# CHIBI_INPUT_20181126.net
KiCad netlist of a schematic drawn in Altium Designer
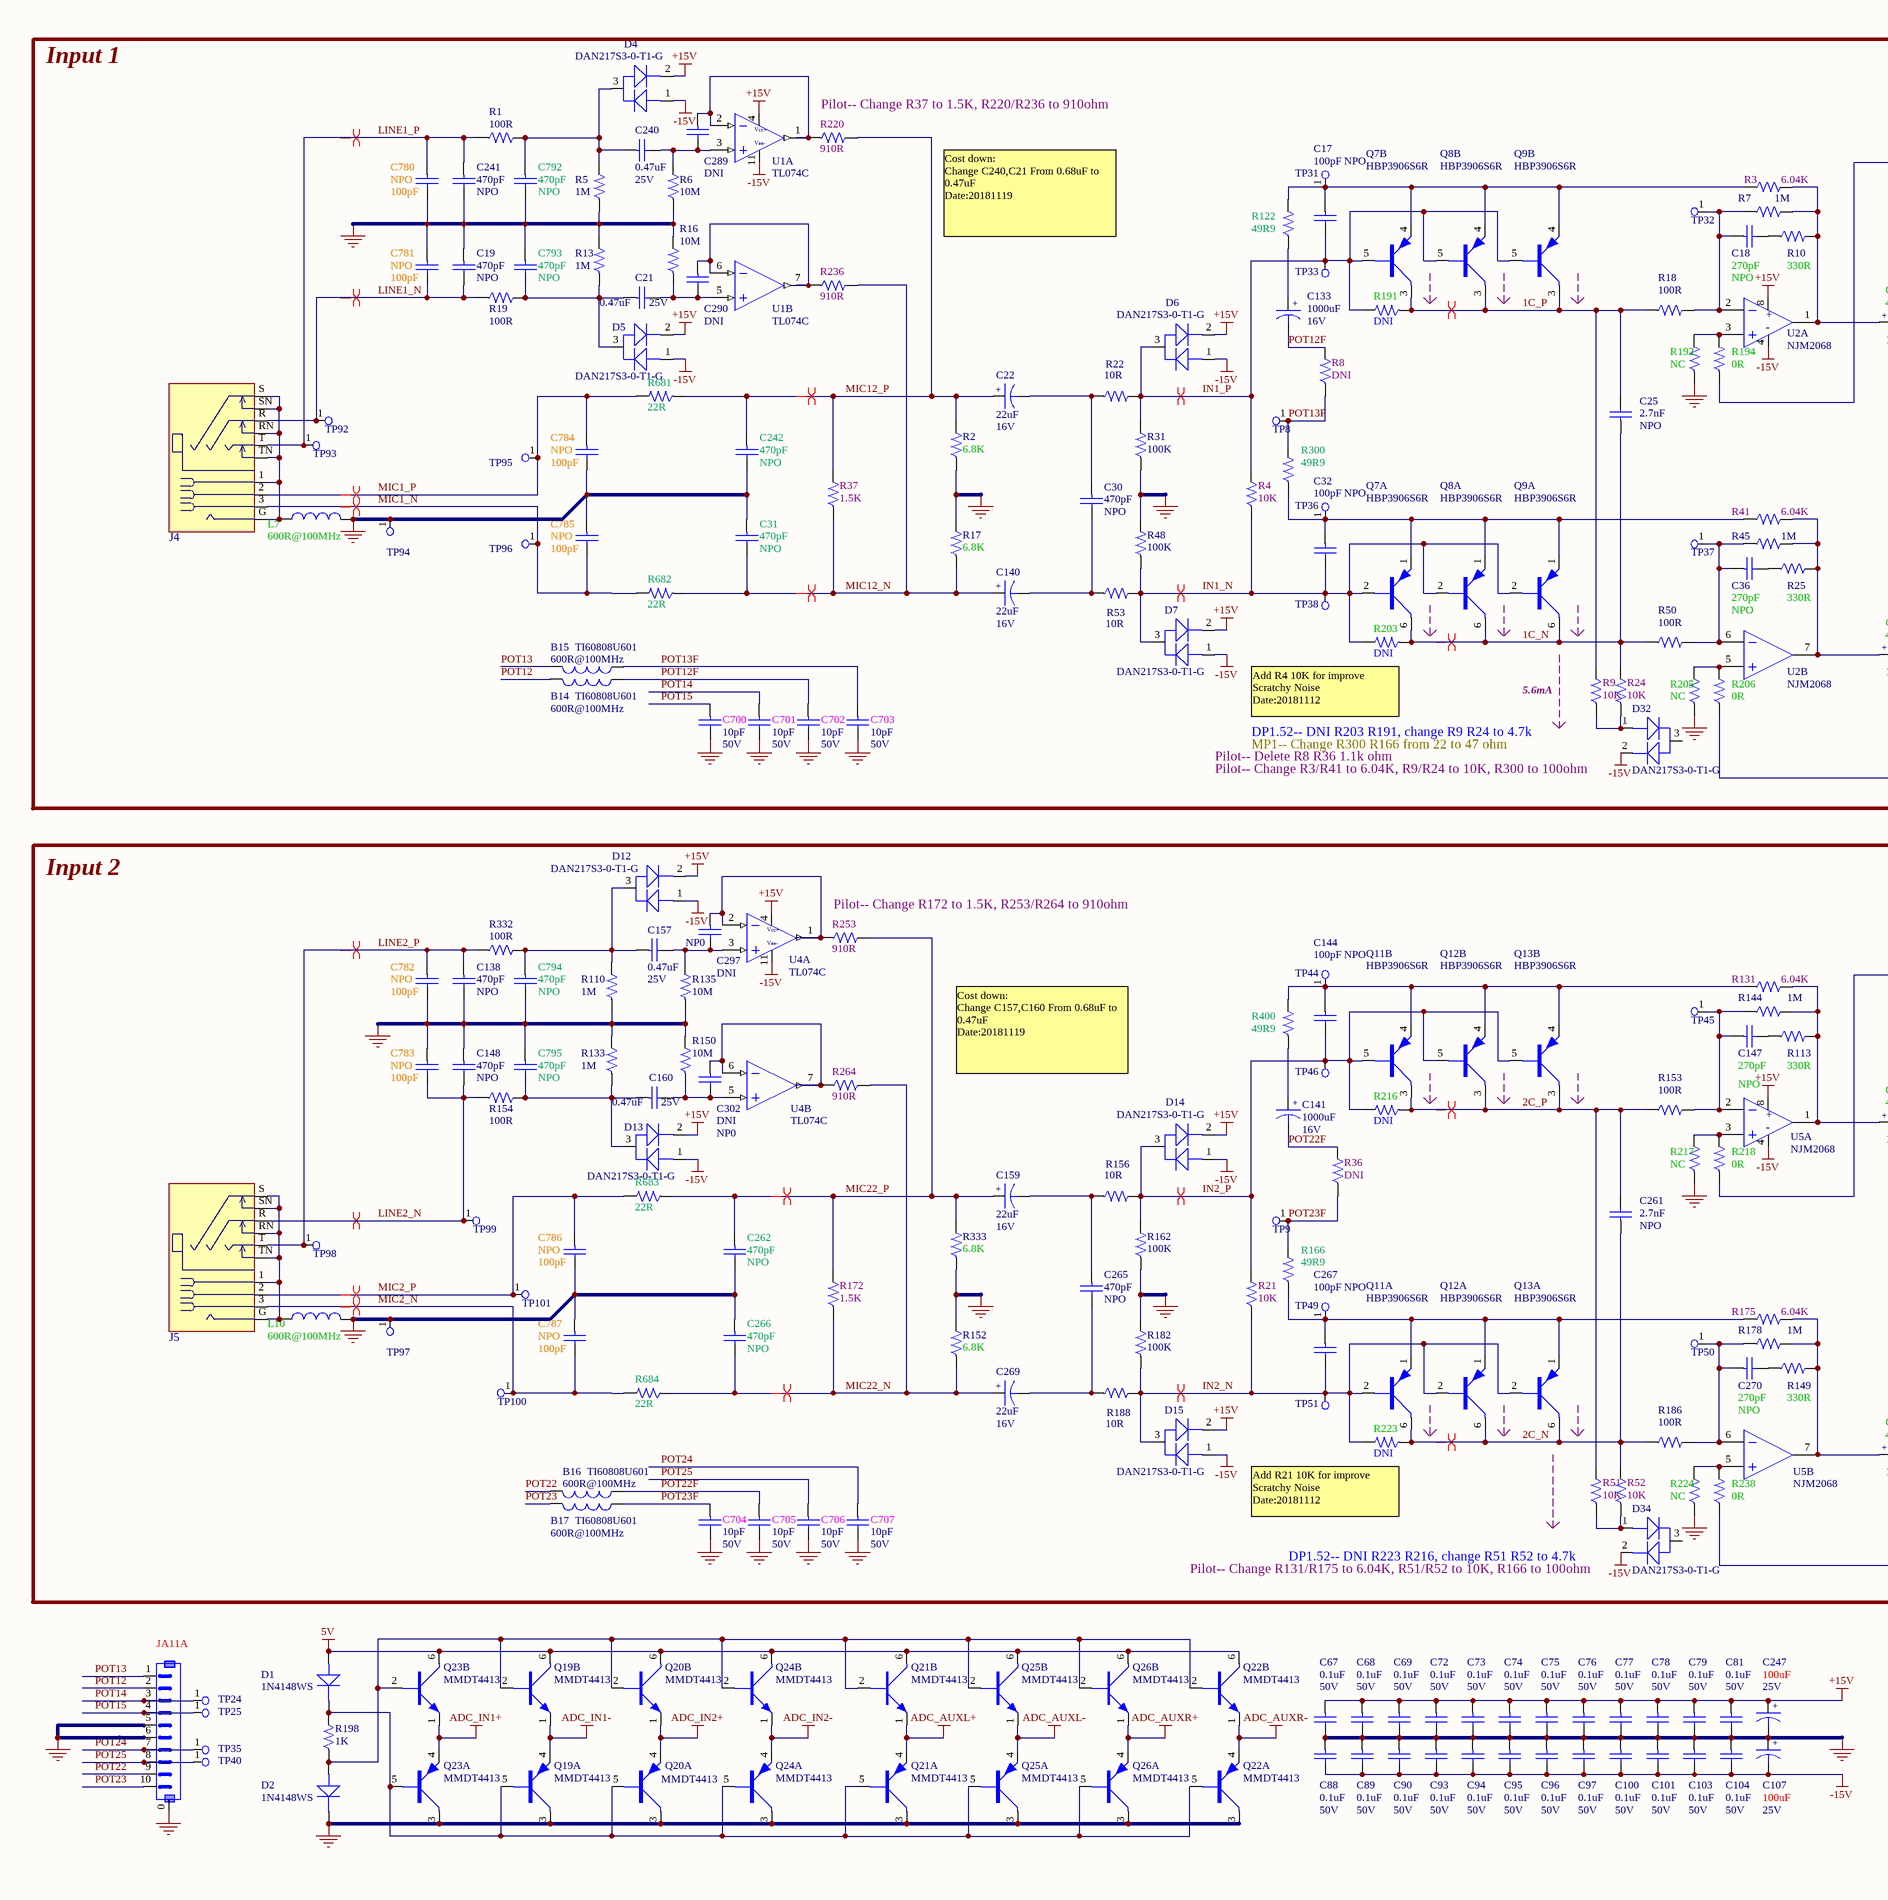
[diagram p0: CHIBI_INPUT_20181126.SchDoc, left]
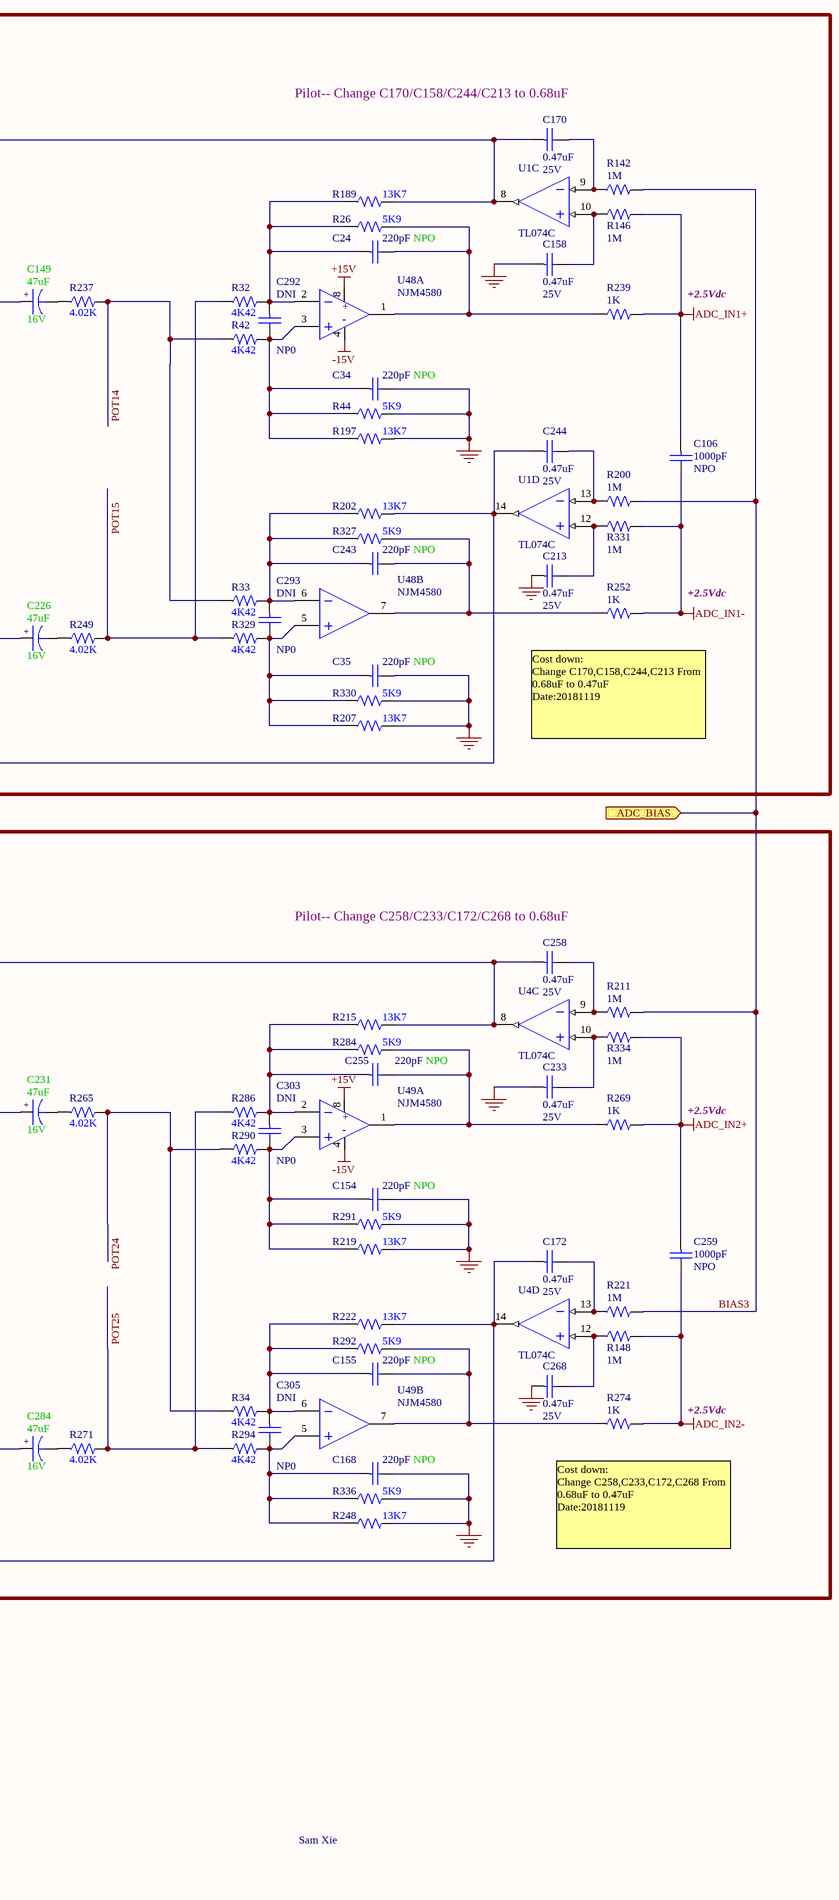
[diagram p1: CHIBI_INPUT_20181126.SchDoc, right]

(export (version "E")
  (design (tool "Eeschema 10.0.6"))
  (components
    (comp (ref "B14")
      (value "600R@100MHz")
      (footprint "L0603-RW")
      (description "CHIP BEAD 600 OHM 25% 100MHZ SMD 0603")
      (fields
        (field (name "MFG") "麦新")
        (field (name "MFG PART") "TI60808U601")
        (field (name "Comment") "SCBA06031-6010")
      )
      (libsource (lib "S-Inductor") (part "BEAD 0603 600R@100MHz TI60808U601"))
    )
    (comp (ref "B15")
      (value "600R@100MHz")
      (footprint "L0603-RW")
      (description "CHIP BEAD 600 OHM 25% 100MHZ SMD 0603")
      (fields
        (field (name "MFG") "麦新")
        (field (name "MFG PART") "TI60808U601")
        (field (name "Comment") "SCBA06031-6010")
      )
      (libsource (lib "S-Inductor") (part "BEAD 0603 600R@100MHz TI60808U601"))
    )
    (comp (ref "B16")
      (value "600R@100MHz")
      (footprint "L0603-RW")
      (description "CHIP BEAD 600 OHM 25% 100MHZ SMD 0603")
      (fields
        (field (name "MFG") "麦新")
        (field (name "MFG PART") "TI60808U601")
        (field (name "Comment") "SCBA06031-6010")
      )
      (libsource (lib "S-Inductor") (part "BEAD 0603 600R@100MHz TI60808U601"))
    )
    (comp (ref "B17")
      (value "600R@100MHz")
      (footprint "L0603-RW")
      (description "CHIP BEAD 600 OHM 25% 100MHZ SMD 0603")
      (fields
        (field (name "MFG") "麦新")
        (field (name "MFG PART") "TI60808U601")
        (field (name "Comment") "SCBA06031-6010")
      )
      (libsource (lib "S-Inductor") (part "BEAD 0603 600R@100MHz TI60808U601"))
    )
    (comp (ref "C17")
      (value "100pF")
      (footprint "CAPC0402-RW")
      (description "CHIP CAP 100pF 50V 5% 0402 TYPE NPO")
      (fields (field (name "MFG") "Walsin") (field (name "OTHER") "NPO") (field (name "TOLERANCE") "5%"))
      (libsource (lib "P-Capacitors") (part "CAP0402 100pF 50V 5%"))
    )
    (comp (ref "C18")
      (value "270pF")
      (footprint "CAPC0603-RW")
      (description "CAP NPO 270PF 50V +-5% 0603 WALSIN L")
      (fields
        (field (name "MFG") "WALSIN")
        (field (name "OTHER") "NPO")
        (field (name "TOLERANCE") "5%")
        (field (name "CREATE_NAME") "Nathan")
      )
      (libsource (lib "P-Capacitors") (part "CAP0603 270pF 50V 5%_NPO_WALSIN"))
    )
    (comp (ref "C19")
      (value "470pF")
      (footprint "CAPC0402-RW")
      (description "CAP CER 470pF 5% 50V NP0/C0G 0402 RoHS")
      (fields
        (field (name "OTHER") "NPO")
        (field (name "TOLERANCE") "5%")
        (field (name "VOLTAGE") "50V")
        (field (name "CREATE_NAME") "TOM@Deftronics")
      )
      (libsource (lib "P-Capacitors") (part "CAP0402 470pF 50V 5% NP0"))
    )
    (comp (ref "C21")
      (value "0.47uF")
      (footprint "CAPC0805X125N-RW")
      (description "CAP X7R .47UF 25V +-10% 0805 WALSIN L")
      (fields
        (field (name "MFG") "WALSIN")
        (field (name "TOLERANCE") "10%")
        (field (name "VOLTAGE") "25V")
        (field (name "CREATE_NAME") "Nathan")
      )
      (libsource (lib "P-Capacitors") (part "CAPC0805 0.47uF 25V 10%_X7R_WALSIN"))
    )
    (comp (ref "C22")
      (value "22uF")
      (footprint "CASE - B")
      (description "E 22UF 16V +-20% 4X5.4M CK1C220M-CRC54 G")
      (fields
        (field (name "MFG") "NORMAL")
        (field (name "MFG PART") "CK1C220M-CRC54")
        (field (name "VOLTAGE") "16V")
      )
      (libsource (lib "P-Capacitors") (part "CAP E 22uF 16V 20% SMD_CASE-B"))
    )
    (comp (ref "C24")
      (value "220pF")
      (footprint "CAPC0603-RW")
      (description "CAP NPO 220PF 50V +-5% 0603 MURATA L")
      (fields
        (field (name "MFG") "MURATA")
        (field (name "OTHER") "NPO")
        (field (name "TOLERANCE") "5%")
        (field (name "CREATE_NAME") "Nathan")
      )
      (libsource (lib "P-Capacitors") (part "CAP0603 220pF 50V 5%_NPO_MURATA"))
    )
    (comp (ref "C25")
      (value "2.7nF")
      (footprint "CAPC0603-RW")
      (description "CHIP CAP 5% 50V 0603 NPO 2.7nF")
      (fields
        (field (name "OTHER") "NPO")
        (field (name "TOLERANCE") "5%")
        (field (name "VOLTAGE") "50V")
        (field (name "CREATE_NAME") "MICHAEL ZHANG")
      )
      (libsource (lib "P-Capacitors") (part "CAP0603 2.7nF 50V 5%"))
    )
    (comp (ref "C30")
      (value "470pF")
      (footprint "CAPC0402-RW")
      (description "CAP CER 470pF 5% 50V NP0/C0G 0402 RoHS")
      (fields
        (field (name "OTHER") "NPO")
        (field (name "TOLERANCE") "5%")
        (field (name "VOLTAGE") "50V")
        (field (name "CREATE_NAME") "TOM@Deftronics")
      )
      (libsource (lib "P-Capacitors") (part "CAP0402 470pF 50V 5% NP0"))
    )
    (comp (ref "C31")
      (value "470pF")
      (footprint "CAPC0402-RW")
      (description "CAP CER 470pF 5% 50V NP0/C0G 0402 RoHS")
      (fields
        (field (name "OTHER") "NPO")
        (field (name "TOLERANCE") "5%")
        (field (name "VOLTAGE") "50V")
        (field (name "CREATE_NAME") "TOM@Deftronics")
      )
      (libsource (lib "P-Capacitors") (part "CAP0402 470pF 50V 5% NP0"))
    )
    (comp (ref "C32")
      (value "100pF")
      (footprint "CAPC0402-RW")
      (description "CHIP CAP 100pF 50V 5% 0402 TYPE NPO")
      (fields (field (name "MFG") "Walsin") (field (name "OTHER") "NPO") (field (name "TOLERANCE") "5%"))
      (libsource (lib "P-Capacitors") (part "CAP0402 100pF 50V 5%"))
    )
    (comp (ref "C34")
      (value "220pF")
      (footprint "CAPC0603-RW")
      (description "CAP NPO 220PF 50V +-5% 0603 MURATA L")
      (fields
        (field (name "MFG") "MURATA")
        (field (name "OTHER") "NPO")
        (field (name "TOLERANCE") "5%")
        (field (name "CREATE_NAME") "Nathan")
      )
      (libsource (lib "P-Capacitors") (part "CAP0603 220pF 50V 5%_NPO_MURATA"))
    )
    (comp (ref "C35")
      (value "220pF")
      (footprint "CAPC0603-RW")
      (description "CAP NPO 220PF 50V +-5% 0603 MURATA L")
      (fields
        (field (name "MFG") "MURATA")
        (field (name "OTHER") "NPO")
        (field (name "TOLERANCE") "5%")
        (field (name "CREATE_NAME") "Nathan")
      )
      (libsource (lib "P-Capacitors") (part "CAP0603 220pF 50V 5%_NPO_MURATA"))
    )
    (comp (ref "C36")
      (value "270pF")
      (footprint "CAPC0603-RW")
      (description "CAP NPO 270PF 50V +-5% 0603 WALSIN L")
      (fields
        (field (name "MFG") "WALSIN")
        (field (name "OTHER") "NPO")
        (field (name "TOLERANCE") "5%")
        (field (name "CREATE_NAME") "Nathan")
      )
      (libsource (lib "P-Capacitors") (part "CAP0603 270pF 50V 5%_NPO_WALSIN"))
    )
    (comp (ref "C67")
      (value "0.1uF")
      (footprint "CAPC0402-RW")
      (description "CAP, CER, 0.1uF, 10%, 50V, X7R, 0402, RoHS")
      (fields
        (field (name "TOLERANCE") "10%")
        (field (name "VOLTAGE") "50V")
        (field (name "Comment") "PWL456470-1040")
        (field (name "CREATE_NAME") "TOM@Deftronics")
      )
      (libsource (lib "P-Capacitors") (part "CAP0402 0.1uF 50V 10%"))
    )
    (comp (ref "C68")
      (value "0.1uF")
      (footprint "CAPC0402-RW")
      (description "CAP, CER, 0.1uF, 10%, 50V, X7R, 0402, RoHS")
      (fields
        (field (name "TOLERANCE") "10%")
        (field (name "VOLTAGE") "50V")
        (field (name "Comment") "PWL456470-1040")
        (field (name "CREATE_NAME") "TOM@Deftronics")
      )
      (libsource (lib "P-Capacitors") (part "CAP0402 0.1uF 50V 10%"))
    )
    (comp (ref "C69")
      (value "0.1uF")
      (footprint "CAPC0402-RW")
      (description "CAP, CER, 0.1uF, 10%, 50V, X7R, 0402, RoHS")
      (fields
        (field (name "TOLERANCE") "10%")
        (field (name "VOLTAGE") "50V")
        (field (name "Comment") "PWL456470-1040")
        (field (name "CREATE_NAME") "TOM@Deftronics")
      )
      (libsource (lib "P-Capacitors") (part "CAP0402 0.1uF 50V 10%"))
    )
    (comp (ref "C72")
      (value "0.1uF")
      (footprint "CAPC0402-RW")
      (description "CAP, CER, 0.1uF, 10%, 50V, X7R, 0402, RoHS")
      (fields
        (field (name "TOLERANCE") "10%")
        (field (name "VOLTAGE") "50V")
        (field (name "Comment") "PWL456470-1040")
        (field (name "CREATE_NAME") "TOM@Deftronics")
      )
      (libsource (lib "P-Capacitors") (part "CAP0402 0.1uF 50V 10%"))
    )
    (comp (ref "C73")
      (value "0.1uF")
      (footprint "CAPC0402-RW")
      (description "CAP, CER, 0.1uF, 10%, 50V, X7R, 0402, RoHS")
      (fields
        (field (name "TOLERANCE") "10%")
        (field (name "VOLTAGE") "50V")
        (field (name "Comment") "PWL456470-1040")
        (field (name "CREATE_NAME") "TOM@Deftronics")
      )
      (libsource (lib "P-Capacitors") (part "CAP0402 0.1uF 50V 10%"))
    )
    (comp (ref "C74")
      (value "0.1uF")
      (footprint "CAPC0402-RW")
      (description "CAP, CER, 0.1uF, 10%, 50V, X7R, 0402, RoHS")
      (fields
        (field (name "TOLERANCE") "10%")
        (field (name "VOLTAGE") "50V")
        (field (name "Comment") "PWL456470-1040")
        (field (name "CREATE_NAME") "TOM@Deftronics")
      )
      (libsource (lib "P-Capacitors") (part "CAP0402 0.1uF 50V 10%"))
    )
    (comp (ref "C75")
      (value "0.1uF")
      (footprint "CAPC0402-RW")
      (description "CAP, CER, 0.1uF, 10%, 50V, X7R, 0402, RoHS")
      (fields
        (field (name "TOLERANCE") "10%")
        (field (name "VOLTAGE") "50V")
        (field (name "Comment") "PWL456470-1040")
        (field (name "CREATE_NAME") "TOM@Deftronics")
      )
      (libsource (lib "P-Capacitors") (part "CAP0402 0.1uF 50V 10%"))
    )
    (comp (ref "C76")
      (value "0.1uF")
      (footprint "CAPC0402-RW")
      (description "CAP, CER, 0.1uF, 10%, 50V, X7R, 0402, RoHS")
      (fields
        (field (name "TOLERANCE") "10%")
        (field (name "VOLTAGE") "50V")
        (field (name "Comment") "PWL456470-1040")
        (field (name "CREATE_NAME") "TOM@Deftronics")
      )
      (libsource (lib "P-Capacitors") (part "CAP0402 0.1uF 50V 10%"))
    )
    (comp (ref "C77")
      (value "0.1uF")
      (footprint "CAPC0402-RW")
      (description "CAP, CER, 0.1uF, 10%, 50V, X7R, 0402, RoHS")
      (fields
        (field (name "TOLERANCE") "10%")
        (field (name "VOLTAGE") "50V")
        (field (name "Comment") "PWL456470-1040")
        (field (name "CREATE_NAME") "TOM@Deftronics")
      )
      (libsource (lib "P-Capacitors") (part "CAP0402 0.1uF 50V 10%"))
    )
    (comp (ref "C78")
      (value "0.1uF")
      (footprint "CAPC0402-RW")
      (description "CAP, CER, 0.1uF, 10%, 50V, X7R, 0402, RoHS")
      (fields
        (field (name "TOLERANCE") "10%")
        (field (name "VOLTAGE") "50V")
        (field (name "Comment") "PWL456470-1040")
        (field (name "CREATE_NAME") "TOM@Deftronics")
      )
      (libsource (lib "P-Capacitors") (part "CAP0402 0.1uF 50V 10%"))
    )
    (comp (ref "C79")
      (value "0.1uF")
      (footprint "CAPC0402-RW")
      (description "CAP, CER, 0.1uF, 10%, 50V, X7R, 0402, RoHS")
      (fields
        (field (name "TOLERANCE") "10%")
        (field (name "VOLTAGE") "50V")
        (field (name "Comment") "PWL456470-1040")
        (field (name "CREATE_NAME") "TOM@Deftronics")
      )
      (libsource (lib "P-Capacitors") (part "CAP0402 0.1uF 50V 10%"))
    )
    (comp (ref "C81")
      (value "0.1uF")
      (footprint "CAPC0402-RW")
      (description "CAP, CER, 0.1uF, 10%, 50V, X7R, 0402, RoHS")
      (fields
        (field (name "TOLERANCE") "10%")
        (field (name "VOLTAGE") "50V")
        (field (name "Comment") "PWL456470-1040")
        (field (name "CREATE_NAME") "TOM@Deftronics")
      )
      (libsource (lib "P-Capacitors") (part "CAP0402 0.1uF 50V 10%"))
    )
    (comp (ref "C88")
      (value "0.1uF")
      (footprint "CAPC0402-RW")
      (description "CAP, CER, 0.1uF, 10%, 50V, X7R, 0402, RoHS")
      (fields
        (field (name "TOLERANCE") "10%")
        (field (name "VOLTAGE") "50V")
        (field (name "Comment") "PWL456470-1040")
        (field (name "CREATE_NAME") "TOM@Deftronics")
      )
      (libsource (lib "P-Capacitors") (part "CAP0402 0.1uF 50V 10%"))
    )
    (comp (ref "C89")
      (value "0.1uF")
      (footprint "CAPC0402-RW")
      (description "CAP, CER, 0.1uF, 10%, 50V, X7R, 0402, RoHS")
      (fields
        (field (name "TOLERANCE") "10%")
        (field (name "VOLTAGE") "50V")
        (field (name "Comment") "PWL456470-1040")
        (field (name "CREATE_NAME") "TOM@Deftronics")
      )
      (libsource (lib "P-Capacitors") (part "CAP0402 0.1uF 50V 10%"))
    )
    (comp (ref "C90")
      (value "0.1uF")
      (footprint "CAPC0402-RW")
      (description "CAP, CER, 0.1uF, 10%, 50V, X7R, 0402, RoHS")
      (fields
        (field (name "TOLERANCE") "10%")
        (field (name "VOLTAGE") "50V")
        (field (name "Comment") "PWL456470-1040")
        (field (name "CREATE_NAME") "TOM@Deftronics")
      )
      (libsource (lib "P-Capacitors") (part "CAP0402 0.1uF 50V 10%"))
    )
    (comp (ref "C93")
      (value "0.1uF")
      (footprint "CAPC0402-RW")
      (description "CAP, CER, 0.1uF, 10%, 50V, X7R, 0402, RoHS")
      (fields
        (field (name "TOLERANCE") "10%")
        (field (name "VOLTAGE") "50V")
        (field (name "Comment") "PWL456470-1040")
        (field (name "CREATE_NAME") "TOM@Deftronics")
      )
      (libsource (lib "P-Capacitors") (part "CAP0402 0.1uF 50V 10%"))
    )
    (comp (ref "C94")
      (value "0.1uF")
      (footprint "CAPC0402-RW")
      (description "CAP, CER, 0.1uF, 10%, 50V, X7R, 0402, RoHS")
      (fields
        (field (name "TOLERANCE") "10%")
        (field (name "VOLTAGE") "50V")
        (field (name "Comment") "PWL456470-1040")
        (field (name "CREATE_NAME") "TOM@Deftronics")
      )
      (libsource (lib "P-Capacitors") (part "CAP0402 0.1uF 50V 10%"))
    )
    (comp (ref "C95")
      (value "0.1uF")
      (footprint "CAPC0402-RW")
      (description "CAP, CER, 0.1uF, 10%, 50V, X7R, 0402, RoHS")
      (fields
        (field (name "TOLERANCE") "10%")
        (field (name "VOLTAGE") "50V")
        (field (name "Comment") "PWL456470-1040")
        (field (name "CREATE_NAME") "TOM@Deftronics")
      )
      (libsource (lib "P-Capacitors") (part "CAP0402 0.1uF 50V 10%"))
    )
    (comp (ref "C96")
      (value "0.1uF")
      (footprint "CAPC0402-RW")
      (description "CAP, CER, 0.1uF, 10%, 50V, X7R, 0402, RoHS")
      (fields
        (field (name "TOLERANCE") "10%")
        (field (name "VOLTAGE") "50V")
        (field (name "Comment") "PWL456470-1040")
        (field (name "CREATE_NAME") "TOM@Deftronics")
      )
      (libsource (lib "P-Capacitors") (part "CAP0402 0.1uF 50V 10%"))
    )
    (comp (ref "C97")
      (value "0.1uF")
      (footprint "CAPC0402-RW")
      (description "CAP, CER, 0.1uF, 10%, 50V, X7R, 0402, RoHS")
      (fields
        (field (name "TOLERANCE") "10%")
        (field (name "VOLTAGE") "50V")
        (field (name "Comment") "PWL456470-1040")
        (field (name "CREATE_NAME") "TOM@Deftronics")
      )
      (libsource (lib "P-Capacitors") (part "CAP0402 0.1uF 50V 10%"))
    )
    (comp (ref "C100")
      (value "0.1uF")
      (footprint "CAPC0402-RW")
      (description "CAP, CER, 0.1uF, 10%, 50V, X7R, 0402, RoHS")
      (fields
        (field (name "TOLERANCE") "10%")
        (field (name "VOLTAGE") "50V")
        (field (name "Comment") "PWL456470-1040")
        (field (name "CREATE_NAME") "TOM@Deftronics")
      )
      (libsource (lib "P-Capacitors") (part "CAP0402 0.1uF 50V 10%"))
    )
    (comp (ref "C101")
      (value "0.1uF")
      (footprint "CAPC0402-RW")
      (description "CAP, CER, 0.1uF, 10%, 50V, X7R, 0402, RoHS")
      (fields
        (field (name "TOLERANCE") "10%")
        (field (name "VOLTAGE") "50V")
        (field (name "Comment") "PWL456470-1040")
        (field (name "CREATE_NAME") "TOM@Deftronics")
      )
      (libsource (lib "P-Capacitors") (part "CAP0402 0.1uF 50V 10%"))
    )
    (comp (ref "C103")
      (value "0.1uF")
      (footprint "CAPC0402-RW")
      (description "CAP, CER, 0.1uF, 10%, 50V, X7R, 0402, RoHS")
      (fields
        (field (name "TOLERANCE") "10%")
        (field (name "VOLTAGE") "50V")
        (field (name "Comment") "PWL456470-1040")
        (field (name "CREATE_NAME") "TOM@Deftronics")
      )
      (libsource (lib "P-Capacitors") (part "CAP0402 0.1uF 50V 10%"))
    )
    (comp (ref "C104")
      (value "0.1uF")
      (footprint "CAPC0402-RW")
      (description "CAP, CER, 0.1uF, 10%, 50V, X7R, 0402, RoHS")
      (fields
        (field (name "TOLERANCE") "10%")
        (field (name "VOLTAGE") "50V")
        (field (name "Comment") "PWL456470-1040")
        (field (name "CREATE_NAME") "TOM@Deftronics")
      )
      (libsource (lib "P-Capacitors") (part "CAP0402 0.1uF 50V 10%"))
    )
    (comp (ref "C106")
      (value "1000pF")
      (footprint "CAPC0603-RW")
      (description "CHIP CAP 1000pF 50V 5% 0603 TYPE NPO")
      (fields (field (name "OTHER") "NPO") (field (name "TOLERANCE") "5%") (field (name "VOLTAGE") "50V"))
      (libsource (lib "P-Capacitors") (part "CAP0603 1000pF 50V 5% - PXL410370-1020"))
    )
    (comp (ref "C107")
      (value "100uF")
      (footprint "CASE - D8")
      (description "E 100UF 25V +-20% 6.3*7. DV101M025 G")
      (fields
        (field (name "MFG") "CAPXON")
        (field (name "MFG PART") "DV101M025E077ETR")
        (field (name "VOLTAGE") "25V")
        (field (name "CREATE_NAME") "Tom")
      )
      (libsource (lib "P-Capacitors") (part "CAP E 100uF 25V 20% SMD"))
    )
    (comp (ref "C133")
      (value "1000uF")
      (footprint "CAP_Radial_D8L16P3.5")
      (description "COND ELECT 1000uF 16V 20% 105C LOW ESR")
      (fields (field (name "MFG") "佳维诚") (field (name "TOLERANCE") "20%") (field (name "VOLTAGE") "16V"))
      (libsource (lib "P-Capacitors") (part "CAP E Aluminum 1000uF 16V 20%"))
    )
    (comp (ref "C138")
      (value "470pF")
      (footprint "CAPC0402-RW")
      (description "CAP CER 470pF 5% 50V NP0/C0G 0402 RoHS")
      (fields
        (field (name "OTHER") "NPO")
        (field (name "TOLERANCE") "5%")
        (field (name "VOLTAGE") "50V")
        (field (name "CREATE_NAME") "TOM@Deftronics")
      )
      (libsource (lib "P-Capacitors") (part "CAP0402 470pF 50V 5% NP0"))
    )
    (comp (ref "C140")
      (value "22uF")
      (footprint "CASE - B")
      (description "E 22UF 16V +-20% 4X5.4M CK1C220M-CRC54 G")
      (fields
        (field (name "MFG") "NORMAL")
        (field (name "MFG PART") "CK1C220M-CRC54")
        (field (name "VOLTAGE") "16V")
      )
      (libsource (lib "P-Capacitors") (part "CAP E 22uF 16V 20% SMD_CASE-B"))
    )
    (comp (ref "C141")
      (value "1000uF")
      (footprint "CAP_Radial_D8L16P3.5")
      (description "COND ELECT 1000uF 16V 20% 105C LOW ESR")
      (fields (field (name "MFG") "佳维诚") (field (name "TOLERANCE") "20%") (field (name "VOLTAGE") "16V"))
      (libsource (lib "P-Capacitors") (part "CAP E Aluminum 1000uF 16V 20%"))
    )
    (comp (ref "C144")
      (value "100pF")
      (footprint "CAPC0402-RW")
      (description "CHIP CAP 100pF 50V 5% 0402 TYPE NPO")
      (fields (field (name "MFG") "Walsin") (field (name "OTHER") "NPO") (field (name "TOLERANCE") "5%"))
      (libsource (lib "P-Capacitors") (part "CAP0402 100pF 50V 5%"))
    )
    (comp (ref "C147")
      (value "270pF")
      (footprint "CAPC0603-RW")
      (description "CAP NPO 270PF 50V +-5% 0603 WALSIN L")
      (fields
        (field (name "MFG") "WALSIN")
        (field (name "OTHER") "NPO")
        (field (name "TOLERANCE") "5%")
        (field (name "CREATE_NAME") "Nathan")
      )
      (libsource (lib "P-Capacitors") (part "CAP0603 270pF 50V 5%_NPO_WALSIN"))
    )
    (comp (ref "C148")
      (value "470pF")
      (footprint "CAPC0402-RW")
      (description "CAP CER 470pF 5% 50V NP0/C0G 0402 RoHS")
      (fields
        (field (name "OTHER") "NPO")
        (field (name "TOLERANCE") "5%")
        (field (name "VOLTAGE") "50V")
        (field (name "CREATE_NAME") "TOM@Deftronics")
      )
      (libsource (lib "P-Capacitors") (part "CAP0402 470pF 50V 5% NP0"))
    )
    (comp (ref "C149")
      (value "47uF")
      (footprint "CASE - C")
      (description "E 47UF 16V +-20% 5X5.4M CK1C470M- G")
      (fields
        (field (name "MFG") "NORMAL")
        (field (name "MFG PART") "CK1C470M-CRD54")
        (field (name "VOLTAGE") "16V")
        (field (name "CREATE_NAME") "Tom")
      )
      (libsource (lib "P-Capacitors") (part "CAP E Aluminum 47uF 16V 20%"))
    )
    (comp (ref "C154")
      (value "220pF")
      (footprint "CAPC0603-RW")
      (description "CAP NPO 220PF 50V +-5% 0603 MURATA L")
      (fields
        (field (name "MFG") "MURATA")
        (field (name "OTHER") "NPO")
        (field (name "TOLERANCE") "5%")
        (field (name "CREATE_NAME") "Nathan")
      )
      (libsource (lib "P-Capacitors") (part "CAP0603 220pF 50V 5%_NPO_MURATA"))
    )
    (comp (ref "C155")
      (value "220pF")
      (footprint "CAPC0603-RW")
      (description "CAP NPO 220PF 50V +-5% 0603 MURATA L")
      (fields
        (field (name "MFG") "MURATA")
        (field (name "OTHER") "NPO")
        (field (name "TOLERANCE") "5%")
        (field (name "CREATE_NAME") "Nathan")
      )
      (libsource (lib "P-Capacitors") (part "CAP0603 220pF 50V 5%_NPO_MURATA"))
    )
    (comp (ref "C157")
      (value "0.47uF")
      (footprint "CAPC0805X125N-RW")
      (description "CAP X7R .47UF 25V +-10% 0805 WALSIN L")
      (fields
        (field (name "MFG") "WALSIN")
        (field (name "TOLERANCE") "10%")
        (field (name "VOLTAGE") "25V")
        (field (name "CREATE_NAME") "Nathan")
      )
      (libsource (lib "P-Capacitors") (part "CAPC0805 0.47uF 25V 10%_X7R_WALSIN"))
    )
    (comp (ref "C158")
      (value "0.47uF")
      (footprint "CAPC0805X125N-RW")
      (description "CAP X7R .47UF 25V +-10% 0805 WALSIN L")
      (fields
        (field (name "MFG") "WALSIN")
        (field (name "TOLERANCE") "10%")
        (field (name "VOLTAGE") "25V")
        (field (name "CREATE_NAME") "Nathan")
      )
      (libsource (lib "P-Capacitors") (part "CAPC0805 0.47uF 25V 10%_X7R_WALSIN"))
    )
    (comp (ref "C159")
      (value "22uF")
      (footprint "CASE - B")
      (description "E 22UF 16V +-20% 4X5.4M CK1C220M-CRC54 G")
      (fields
        (field (name "MFG") "NORMAL")
        (field (name "MFG PART") "CK1C220M-CRC54")
        (field (name "VOLTAGE") "16V")
      )
      (libsource (lib "P-Capacitors") (part "CAP E 22uF 16V 20% SMD_CASE-B"))
    )
    (comp (ref "C160")
      (value "0.47uF")
      (footprint "CAPC0805X125N-RW")
      (description "CAP X7R .47UF 25V +-10% 0805 WALSIN L")
      (fields
        (field (name "MFG") "WALSIN")
        (field (name "TOLERANCE") "10%")
        (field (name "VOLTAGE") "25V")
        (field (name "CREATE_NAME") "Nathan")
      )
      (libsource (lib "P-Capacitors") (part "CAPC0805 0.47uF 25V 10%_X7R_WALSIN"))
    )
    (comp (ref "C168")
      (value "220pF")
      (footprint "CAPC0603-RW")
      (description "CAP NPO 220PF 50V +-5% 0603 MURATA L")
      (fields
        (field (name "MFG") "MURATA")
        (field (name "OTHER") "NPO")
        (field (name "TOLERANCE") "5%")
        (field (name "CREATE_NAME") "Nathan")
      )
      (libsource (lib "P-Capacitors") (part "CAP0603 220pF 50V 5%_NPO_MURATA"))
    )
    (comp (ref "C170")
      (value "0.47uF")
      (footprint "CAPC0805X125N-RW")
      (description "CAP X7R .47UF 25V +-10% 0805 WALSIN L")
      (fields
        (field (name "MFG") "WALSIN")
        (field (name "TOLERANCE") "10%")
        (field (name "VOLTAGE") "25V")
        (field (name "CREATE_NAME") "Nathan")
      )
      (libsource (lib "P-Capacitors") (part "CAPC0805 0.47uF 25V 10%_X7R_WALSIN"))
    )
    (comp (ref "C172")
      (value "0.47uF")
      (footprint "CAPC0805X125N-RW")
      (description "CAP X7R .47UF 25V +-10% 0805 WALSIN L")
      (fields
        (field (name "MFG") "WALSIN")
        (field (name "TOLERANCE") "10%")
        (field (name "VOLTAGE") "25V")
        (field (name "CREATE_NAME") "Nathan")
      )
      (libsource (lib "P-Capacitors") (part "CAPC0805 0.47uF 25V 10%_X7R_WALSIN"))
    )
    (comp (ref "C213")
      (value "0.47uF")
      (footprint "CAPC0805X125N-RW")
      (description "CAP X7R .47UF 25V +-10% 0805 WALSIN L")
      (fields
        (field (name "MFG") "WALSIN")
        (field (name "TOLERANCE") "10%")
        (field (name "VOLTAGE") "25V")
        (field (name "CREATE_NAME") "Nathan")
      )
      (libsource (lib "P-Capacitors") (part "CAPC0805 0.47uF 25V 10%_X7R_WALSIN"))
    )
    (comp (ref "C226")
      (value "47uF")
      (footprint "CASE - C")
      (description "E 47UF 16V +-20% 5X5.4M CK1C470M- G")
      (fields
        (field (name "MFG") "NORMAL")
        (field (name "MFG PART") "CK1C470M-CRD54")
        (field (name "VOLTAGE") "16V")
        (field (name "CREATE_NAME") "Tom")
      )
      (libsource (lib "P-Capacitors") (part "CAP E Aluminum 47uF 16V 20%"))
    )
    (comp (ref "C231")
      (value "47uF")
      (footprint "CASE - C")
      (description "E 47UF 16V +-20% 5X5.4M CK1C470M- G")
      (fields
        (field (name "MFG") "NORMAL")
        (field (name "MFG PART") "CK1C470M-CRD54")
        (field (name "VOLTAGE") "16V")
        (field (name "CREATE_NAME") "Tom")
      )
      (libsource (lib "P-Capacitors") (part "CAP E Aluminum 47uF 16V 20%"))
    )
    (comp (ref "C233")
      (value "0.47uF")
      (footprint "CAPC0805X125N-RW")
      (description "CAP X7R .47UF 25V +-10% 0805 WALSIN L")
      (fields
        (field (name "MFG") "WALSIN")
        (field (name "TOLERANCE") "10%")
        (field (name "VOLTAGE") "25V")
        (field (name "CREATE_NAME") "Nathan")
      )
      (libsource (lib "P-Capacitors") (part "CAPC0805 0.47uF 25V 10%_X7R_WALSIN"))
    )
    (comp (ref "C240")
      (value "0.47uF")
      (footprint "CAPC0805X125N-RW")
      (description "CAP X7R .47UF 25V +-10% 0805 WALSIN L")
      (fields
        (field (name "MFG") "WALSIN")
        (field (name "TOLERANCE") "10%")
        (field (name "VOLTAGE") "25V")
        (field (name "CREATE_NAME") "Nathan")
      )
      (libsource (lib "P-Capacitors") (part "CAPC0805 0.47uF 25V 10%_X7R_WALSIN"))
    )
    (comp (ref "C241")
      (value "470pF")
      (footprint "CAPC0402-RW")
      (description "CAP CER 470pF 5% 50V NP0/C0G 0402 RoHS")
      (fields
        (field (name "OTHER") "NPO")
        (field (name "TOLERANCE") "5%")
        (field (name "VOLTAGE") "50V")
        (field (name "CREATE_NAME") "TOM@Deftronics")
      )
      (libsource (lib "P-Capacitors") (part "CAP0402 470pF 50V 5% NP0"))
    )
    (comp (ref "C242")
      (value "470pF")
      (footprint "CAPC0402-RW")
      (description "CAP CER 470pF 5% 50V NP0/C0G 0402 RoHS")
      (fields
        (field (name "OTHER") "NPO")
        (field (name "TOLERANCE") "5%")
        (field (name "VOLTAGE") "50V")
        (field (name "CREATE_NAME") "TOM@Deftronics")
      )
      (libsource (lib "P-Capacitors") (part "CAP0402 470pF 50V 5% NP0"))
    )
    (comp (ref "C243")
      (value "220pF")
      (footprint "CAPC0603-RW")
      (description "CAP NPO 220PF 50V +-5% 0603 MURATA L")
      (fields
        (field (name "MFG") "MURATA")
        (field (name "OTHER") "NPO")
        (field (name "TOLERANCE") "5%")
        (field (name "CREATE_NAME") "Nathan")
      )
      (libsource (lib "P-Capacitors") (part "CAP0603 220pF 50V 5%_NPO_MURATA"))
    )
    (comp (ref "C244")
      (value "0.47uF")
      (footprint "CAPC0805X125N-RW")
      (description "CAP X7R .47UF 25V +-10% 0805 WALSIN L")
      (fields
        (field (name "MFG") "WALSIN")
        (field (name "TOLERANCE") "10%")
        (field (name "VOLTAGE") "25V")
        (field (name "CREATE_NAME") "Nathan")
      )
      (libsource (lib "P-Capacitors") (part "CAPC0805 0.47uF 25V 10%_X7R_WALSIN"))
    )
    (comp (ref "C247")
      (value "100uF")
      (footprint "CASE - D8")
      (description "E 100UF 25V +-20% 6.3*7. DV101M025 G")
      (fields
        (field (name "MFG") "CAPXON")
        (field (name "MFG PART") "DV101M025E077ETR")
        (field (name "VOLTAGE") "25V")
        (field (name "CREATE_NAME") "Tom")
      )
      (libsource (lib "P-Capacitors") (part "CAP E 100uF 25V 20% SMD"))
    )
    (comp (ref "C255")
      (value "220pF")
      (footprint "CAPC0603-RW")
      (description "CAP NPO 220PF 50V +-5% 0603 MURATA L")
      (fields
        (field (name "MFG") "MURATA")
        (field (name "OTHER") "NPO")
        (field (name "TOLERANCE") "5%")
        (field (name "CREATE_NAME") "Nathan")
      )
      (libsource (lib "P-Capacitors") (part "CAP0603 220pF 50V 5%_NPO_MURATA"))
    )
    (comp (ref "C258")
      (value "0.47uF")
      (footprint "CAPC0805X125N-RW")
      (description "CAP X7R .47UF 25V +-10% 0805 WALSIN L")
      (fields
        (field (name "MFG") "WALSIN")
        (field (name "TOLERANCE") "10%")
        (field (name "VOLTAGE") "25V")
        (field (name "CREATE_NAME") "Nathan")
      )
      (libsource (lib "P-Capacitors") (part "CAPC0805 0.47uF 25V 10%_X7R_WALSIN"))
    )
    (comp (ref "C259")
      (value "1000pF")
      (footprint "CAPC0603-RW")
      (description "CHIP CAP 1000pF 50V 5% 0603 TYPE NPO")
      (fields (field (name "OTHER") "NPO") (field (name "TOLERANCE") "5%") (field (name "VOLTAGE") "50V"))
      (libsource (lib "P-Capacitors") (part "CAP0603 1000pF 50V 5% - PXL410370-1020"))
    )
    (comp (ref "C261")
      (value "2.7nF")
      (footprint "CAPC0603-RW")
      (description "CHIP CAP 5% 50V 0603 NPO 2.7nF")
      (fields
        (field (name "OTHER") "NPO")
        (field (name "TOLERANCE") "5%")
        (field (name "VOLTAGE") "50V")
        (field (name "CREATE_NAME") "MICHAEL ZHANG")
      )
      (libsource (lib "P-Capacitors") (part "CAP0603 2.7nF 50V 5%"))
    )
    (comp (ref "C262")
      (value "470pF")
      (footprint "CAPC0402-RW")
      (description "CAP CER 470pF 5% 50V NP0/C0G 0402 RoHS")
      (fields
        (field (name "OTHER") "NPO")
        (field (name "TOLERANCE") "5%")
        (field (name "VOLTAGE") "50V")
        (field (name "CREATE_NAME") "TOM@Deftronics")
      )
      (libsource (lib "P-Capacitors") (part "CAP0402 470pF 50V 5% NP0"))
    )
    (comp (ref "C265")
      (value "470pF")
      (footprint "CAPC0402-RW")
      (description "CAP CER 470pF 5% 50V NP0/C0G 0402 RoHS")
      (fields
        (field (name "OTHER") "NPO")
        (field (name "TOLERANCE") "5%")
        (field (name "VOLTAGE") "50V")
        (field (name "CREATE_NAME") "TOM@Deftronics")
      )
      (libsource (lib "P-Capacitors") (part "CAP0402 470pF 50V 5% NP0"))
    )
    (comp (ref "C266")
      (value "470pF")
      (footprint "CAPC0402-RW")
      (description "CAP CER 470pF 5% 50V NP0/C0G 0402 RoHS")
      (fields
        (field (name "OTHER") "NPO")
        (field (name "TOLERANCE") "5%")
        (field (name "VOLTAGE") "50V")
        (field (name "CREATE_NAME") "TOM@Deftronics")
      )
      (libsource (lib "P-Capacitors") (part "CAP0402 470pF 50V 5% NP0"))
    )
    (comp (ref "C267")
      (value "100pF")
      (footprint "CAPC0402-RW")
      (description "CHIP CAP 100pF 50V 5% 0402 TYPE NPO")
      (fields (field (name "MFG") "Walsin") (field (name "OTHER") "NPO") (field (name "TOLERANCE") "5%"))
      (libsource (lib "P-Capacitors") (part "CAP0402 100pF 50V 5%"))
    )
    (comp (ref "C268")
      (value "0.47uF")
      (footprint "CAPC0805X125N-RW")
      (description "CAP X7R .47UF 25V +-10% 0805 WALSIN L")
      (fields
        (field (name "MFG") "WALSIN")
        (field (name "TOLERANCE") "10%")
        (field (name "VOLTAGE") "25V")
        (field (name "CREATE_NAME") "Nathan")
      )
      (libsource (lib "P-Capacitors") (part "CAPC0805 0.47uF 25V 10%_X7R_WALSIN"))
    )
    (comp (ref "C269")
      (value "22uF")
      (footprint "CASE - B")
      (description "E 22UF 16V +-20% 4X5.4M CK1C220M-CRC54 G")
      (fields
        (field (name "MFG") "NORMAL")
        (field (name "MFG PART") "CK1C220M-CRC54")
        (field (name "VOLTAGE") "16V")
      )
      (libsource (lib "P-Capacitors") (part "CAP E 22uF 16V 20% SMD_CASE-B"))
    )
    (comp (ref "C270")
      (value "270pF")
      (footprint "CAPC0603-RW")
      (description "CAP NPO 270PF 50V +-5% 0603 WALSIN L")
      (fields
        (field (name "MFG") "WALSIN")
        (field (name "OTHER") "NPO")
        (field (name "TOLERANCE") "5%")
        (field (name "CREATE_NAME") "Nathan")
      )
      (libsource (lib "P-Capacitors") (part "CAP0603 270pF 50V 5%_NPO_WALSIN"))
    )
    (comp (ref "C284")
      (value "47uF")
      (footprint "CASE - C")
      (description "E 47UF 16V +-20% 5X5.4M CK1C470M- G")
      (fields
        (field (name "MFG") "NORMAL")
        (field (name "MFG PART") "CK1C470M-CRD54")
        (field (name "VOLTAGE") "16V")
        (field (name "CREATE_NAME") "Tom")
      )
      (libsource (lib "P-Capacitors") (part "CAP E Aluminum 47uF 16V 20%"))
    )
    (comp (ref "C289")
      (value "DNI")
      (footprint "CAPC0402-RW")
      (fields
        (field (name "TOLERANCE") "10%")
        (field (name "VOLTAGE") "50V")
        (field (name "CREATE_NAME") "Nathan")
      )
      (libsource (lib "P-Capacitors") (part "CAP0402 0.1uF 50V_10%_X7R_TDK"))
    )
    (comp (ref "C290")
      (value "DNI")
      (footprint "CAPC0402-RW")
      (fields
        (field (name "TOLERANCE") "10%")
        (field (name "VOLTAGE") "50V")
        (field (name "CREATE_NAME") "Nathan")
      )
      (libsource (lib "P-Capacitors") (part "CAP0402 0.1uF 50V_10%_X7R_TDK"))
    )
    (comp (ref "C292")
      (value "DNI")
      (footprint "CAPC0402-RW")
      (fields
        (field (name "OTHER") "NP0")
        (field (name "TOLERANCE") "10%")
        (field (name "VOLTAGE") "50V")
        (field (name "CREATE_NAME") "Nathan")
      )
      (libsource (lib "P-Capacitors") (part "CAP0402 0.1uF 50V_10%_X7R_TDK"))
    )
    (comp (ref "C293")
      (value "DNI")
      (footprint "CAPC0402-RW")
      (fields
        (field (name "OTHER") "NP0")
        (field (name "TOLERANCE") "10%")
        (field (name "VOLTAGE") "50V")
        (field (name "CREATE_NAME") "Nathan")
      )
      (libsource (lib "P-Capacitors") (part "CAP0402 0.1uF 50V_10%_X7R_TDK"))
    )
    (comp (ref "C297")
      (value "DNI")
      (footprint "CAPC0402-RW")
      (fields
        (field (name "OTHER") "NP0")
        (field (name "TOLERANCE") "10%")
        (field (name "VOLTAGE") "50V")
        (field (name "CREATE_NAME") "Nathan")
      )
      (libsource (lib "P-Capacitors") (part "CAP0402 0.1uF 50V_10%_X7R_TDK"))
    )
    (comp (ref "C302")
      (value "DNI")
      (footprint "CAPC0402-RW")
      (fields
        (field (name "OTHER") "NP0")
        (field (name "TOLERANCE") "10%")
        (field (name "VOLTAGE") "50V")
        (field (name "CREATE_NAME") "Nathan")
      )
      (libsource (lib "P-Capacitors") (part "CAP0402 0.1uF 50V_10%_X7R_TDK"))
    )
    (comp (ref "C303")
      (value "DNI")
      (footprint "CAPC0402-RW")
      (fields
        (field (name "OTHER") "NP0")
        (field (name "TOLERANCE") "10%")
        (field (name "VOLTAGE") "50V")
        (field (name "CREATE_NAME") "Nathan")
      )
      (libsource (lib "P-Capacitors") (part "CAP0402 0.1uF 50V_10%_X7R_TDK"))
    )
    (comp (ref "C305")
      (value "DNI")
      (footprint "CAPC0402-RW")
      (fields
        (field (name "OTHER") "NP0")
        (field (name "TOLERANCE") "10%")
        (field (name "VOLTAGE") "50V")
        (field (name "CREATE_NAME") "Nathan")
      )
      (libsource (lib "P-Capacitors") (part "CAP0402 0.1uF 50V_10%_X7R_TDK"))
    )
    (comp (ref "C700")
      (value "10pF")
      (footprint "CAPC0402-RW")
      (description "CHIP CAP 5% 50V 0402 NPO 10pF")
      (fields
        (field (name "TOLERANCE") "5%")
        (field (name "VOLTAGE") "50V")
        (field (name "Comment") "PWL410371-1000")
        (field (name "CREATE_NAME") "TOM@Deftronics")
      )
      (libsource (lib "P-Capacitors") (part "CAP0402 10pF 50V 5%"))
    )
    (comp (ref "C701")
      (value "10pF")
      (footprint "CAPC0402-RW")
      (description "CHIP CAP 5% 50V 0402 NPO 10pF")
      (fields
        (field (name "TOLERANCE") "5%")
        (field (name "VOLTAGE") "50V")
        (field (name "Comment") "PWL410371-1000")
        (field (name "CREATE_NAME") "TOM@Deftronics")
      )
      (libsource (lib "P-Capacitors") (part "CAP0402 10pF 50V 5%"))
    )
    (comp (ref "C702")
      (value "10pF")
      (footprint "CAPC0402-RW")
      (description "CHIP CAP 5% 50V 0402 NPO 10pF")
      (fields
        (field (name "TOLERANCE") "5%")
        (field (name "VOLTAGE") "50V")
        (field (name "Comment") "PWL410371-1000")
        (field (name "CREATE_NAME") "TOM@Deftronics")
      )
      (libsource (lib "P-Capacitors") (part "CAP0402 10pF 50V 5%"))
    )
    (comp (ref "C703")
      (value "10pF")
      (footprint "CAPC0402-RW")
      (description "CHIP CAP 5% 50V 0402 NPO 10pF")
      (fields
        (field (name "TOLERANCE") "5%")
        (field (name "VOLTAGE") "50V")
        (field (name "Comment") "PWL410371-1000")
        (field (name "CREATE_NAME") "TOM@Deftronics")
      )
      (libsource (lib "P-Capacitors") (part "CAP0402 10pF 50V 5%"))
    )
    (comp (ref "C704")
      (value "10pF")
      (footprint "CAPC0402-RW")
      (description "CHIP CAP 5% 50V 0402 NPO 10pF")
      (fields
        (field (name "TOLERANCE") "5%")
        (field (name "VOLTAGE") "50V")
        (field (name "Comment") "PWL410371-1000")
        (field (name "CREATE_NAME") "TOM@Deftronics")
      )
      (libsource (lib "P-Capacitors") (part "CAP0402 10pF 50V 5%"))
    )
    (comp (ref "C705")
      (value "10pF")
      (footprint "CAPC0402-RW")
      (description "CHIP CAP 5% 50V 0402 NPO 10pF")
      (fields
        (field (name "TOLERANCE") "5%")
        (field (name "VOLTAGE") "50V")
        (field (name "Comment") "PWL410371-1000")
        (field (name "CREATE_NAME") "TOM@Deftronics")
      )
      (libsource (lib "P-Capacitors") (part "CAP0402 10pF 50V 5%"))
    )
    (comp (ref "C706")
      (value "10pF")
      (footprint "CAPC0402-RW")
      (description "CHIP CAP 5% 50V 0402 NPO 10pF")
      (fields
        (field (name "TOLERANCE") "5%")
        (field (name "VOLTAGE") "50V")
        (field (name "Comment") "PWL410371-1000")
        (field (name "CREATE_NAME") "TOM@Deftronics")
      )
      (libsource (lib "P-Capacitors") (part "CAP0402 10pF 50V 5%"))
    )
    (comp (ref "C707")
      (value "10pF")
      (footprint "CAPC0402-RW")
      (description "CHIP CAP 5% 50V 0402 NPO 10pF")
      (fields
        (field (name "TOLERANCE") "5%")
        (field (name "VOLTAGE") "50V")
        (field (name "Comment") "PWL410371-1000")
        (field (name "CREATE_NAME") "TOM@Deftronics")
      )
      (libsource (lib "P-Capacitors") (part "CAP0402 10pF 50V 5%"))
    )
    (comp (ref "C780")
      (value "100pF")
      (footprint "CAPC0402-RW")
      (description "CHIP CAP 100pF 50V 5% 0402 TYPE NPO")
      (fields (field (name "MFG") "Walsin") (field (name "OTHER") "NPO") (field (name "TOLERANCE") "5%"))
      (libsource (lib "P-Capacitors") (part "CAP0402 100pF 50V 5%"))
    )
    (comp (ref "C781")
      (value "100pF")
      (footprint "CAPC0402-RW")
      (description "CHIP CAP 100pF 50V 5% 0402 TYPE NPO")
      (fields (field (name "MFG") "Walsin") (field (name "OTHER") "NPO") (field (name "TOLERANCE") "5%"))
      (libsource (lib "P-Capacitors") (part "CAP0402 100pF 50V 5%"))
    )
    (comp (ref "C782")
      (value "100pF")
      (footprint "CAPC0402-RW")
      (description "CHIP CAP 100pF 50V 5% 0402 TYPE NPO")
      (fields (field (name "MFG") "Walsin") (field (name "OTHER") "NPO") (field (name "TOLERANCE") "5%"))
      (libsource (lib "P-Capacitors") (part "CAP0402 100pF 50V 5%"))
    )
    (comp (ref "C783")
      (value "100pF")
      (footprint "CAPC0402-RW")
      (description "CHIP CAP 100pF 50V 5% 0402 TYPE NPO")
      (fields (field (name "MFG") "Walsin") (field (name "OTHER") "NPO") (field (name "TOLERANCE") "5%"))
      (libsource (lib "P-Capacitors") (part "CAP0402 100pF 50V 5%"))
    )
    (comp (ref "C784")
      (value "100pF")
      (footprint "CAPC0402-RW")
      (description "CHIP CAP 100pF 50V 5% 0402 TYPE NPO")
      (fields (field (name "MFG") "Walsin") (field (name "OTHER") "NPO") (field (name "TOLERANCE") "5%"))
      (libsource (lib "P-Capacitors") (part "CAP0402 100pF 50V 5%"))
    )
    (comp (ref "C785")
      (value "100pF")
      (footprint "CAPC0402-RW")
      (description "CHIP CAP 100pF 50V 5% 0402 TYPE NPO")
      (fields (field (name "MFG") "Walsin") (field (name "OTHER") "NPO") (field (name "TOLERANCE") "5%"))
      (libsource (lib "P-Capacitors") (part "CAP0402 100pF 50V 5%"))
    )
    (comp (ref "C786")
      (value "100pF")
      (footprint "CAPC0402-RW")
      (description "CHIP CAP 100pF 50V 5% 0402 TYPE NPO")
      (fields (field (name "MFG") "Walsin") (field (name "OTHER") "NPO") (field (name "TOLERANCE") "5%"))
      (libsource (lib "P-Capacitors") (part "CAP0402 100pF 50V 5%"))
    )
    (comp (ref "C787")
      (value "100pF")
      (footprint "CAPC0402-RW")
      (description "CHIP CAP 100pF 50V 5% 0402 TYPE NPO")
      (fields (field (name "MFG") "Walsin") (field (name "OTHER") "NPO") (field (name "TOLERANCE") "5%"))
      (libsource (lib "P-Capacitors") (part "CAP0402 100pF 50V 5%"))
    )
    (comp (ref "C792")
      (value "470pF")
      (footprint "CAPC0402-RW")
      (description "CAP CER 470pF 5% 50V NP0/C0G 0402 RoHS")
      (fields
        (field (name "OTHER") "NPO")
        (field (name "TOLERANCE") "5%")
        (field (name "VOLTAGE") "50V")
        (field (name "CREATE_NAME") "TOM@Deftronics")
      )
      (libsource (lib "P-Capacitors") (part "CAP0402 470pF 50V 5% NP0"))
    )
    (comp (ref "C793")
      (value "470pF")
      (footprint "CAPC0402-RW")
      (description "CAP CER 470pF 5% 50V NP0/C0G 0402 RoHS")
      (fields
        (field (name "OTHER") "NPO")
        (field (name "TOLERANCE") "5%")
        (field (name "VOLTAGE") "50V")
        (field (name "CREATE_NAME") "TOM@Deftronics")
      )
      (libsource (lib "P-Capacitors") (part "CAP0402 470pF 50V 5% NP0"))
    )
    (comp (ref "C794")
      (value "470pF")
      (footprint "CAPC0402-RW")
      (description "CAP CER 470pF 5% 50V NP0/C0G 0402 RoHS")
      (fields
        (field (name "OTHER") "NPO")
        (field (name "TOLERANCE") "5%")
        (field (name "VOLTAGE") "50V")
        (field (name "CREATE_NAME") "TOM@Deftronics")
      )
      (libsource (lib "P-Capacitors") (part "CAP0402 470pF 50V 5% NP0"))
    )
    (comp (ref "C795")
      (value "470pF")
      (footprint "CAPC0402-RW")
      (description "CAP CER 470pF 5% 50V NP0/C0G 0402 RoHS")
      (fields
        (field (name "OTHER") "NPO")
        (field (name "TOLERANCE") "5%")
        (field (name "VOLTAGE") "50V")
        (field (name "CREATE_NAME") "TOM@Deftronics")
      )
      (libsource (lib "P-Capacitors") (part "CAP0402 470pF 50V 5% NP0"))
    )
    (comp (ref "D1")
      (value "RCD114148-0020")
      (footprint "SOD-323")
      (description "DIODE SW 1N4148 VF=0.7V SOD-323")
      (fields
        (field (name "MFG") "TW SEMICONDUCTOR")
        (field (name "VOLTAGE") "100V")
        (field (name "MFG PART") "1N4148WS")
      )
      (libsource (lib "R-Semiconductors") (part "1N4148WS"))
    )
    (comp (ref "D2")
      (value "RCD114148-0020")
      (footprint "SOD-323")
      (description "DIODE SW 1N4148 VF=0.7V SOD-323")
      (fields
        (field (name "MFG") "TW SEMICONDUCTOR")
        (field (name "VOLTAGE") "100V")
        (field (name "MFG PART") "1N4148WS")
      )
      (libsource (lib "R-Semiconductors") (part "1N4148WS"))
    )
    (comp (ref "D4")
      (value "T572006171251")
      (footprint "SOT323(SC-70)-R")
      (description "ITC 100V 215MA DAN217S3-0-T1-G CYSTE K")
      (fields
        (field (name "MFG") "CYSTECH")
        (field (name "MFG PART") "DAN217S3-0-T1-G")
        (field (name "CREATE NAME") "Nathan")
      )
      (libsource (lib "R-Semiconductors") (part "DAN217S3-0-T1-G"))
    )
    (comp (ref "D5")
      (value "T572006171251")
      (footprint "SOT323(SC-70)-R")
      (description "ITC 100V 215MA DAN217S3-0-T1-G CYSTE K")
      (fields
        (field (name "MFG") "CYSTECH")
        (field (name "MFG PART") "DAN217S3-0-T1-G")
        (field (name "CREATE NAME") "Nathan")
      )
      (libsource (lib "R-Semiconductors") (part "DAN217S3-0-T1-G"))
    )
    (comp (ref "D6")
      (value "T572006171251")
      (footprint "SOT323(SC-70)-R")
      (description "ITC 100V 215MA DAN217S3-0-T1-G CYSTE K")
      (fields
        (field (name "MFG") "CYSTECH")
        (field (name "MFG PART") "DAN217S3-0-T1-G")
        (field (name "CREATE NAME") "Nathan")
      )
      (libsource (lib "R-Semiconductors") (part "DAN217S3-0-T1-G"))
    )
    (comp (ref "D7")
      (value "T572006171251")
      (footprint "SOT323(SC-70)-R")
      (description "ITC 100V 215MA DAN217S3-0-T1-G CYSTE K")
      (fields
        (field (name "MFG") "CYSTECH")
        (field (name "MFG PART") "DAN217S3-0-T1-G")
        (field (name "CREATE NAME") "Nathan")
      )
      (libsource (lib "R-Semiconductors") (part "DAN217S3-0-T1-G"))
    )
    (comp (ref "D12")
      (value "T572006171251")
      (footprint "SOT323(SC-70)-R")
      (description "ITC 100V 215MA DAN217S3-0-T1-G CYSTE K")
      (fields
        (field (name "MFG") "CYSTECH")
        (field (name "MFG PART") "DAN217S3-0-T1-G")
        (field (name "CREATE NAME") "Nathan")
      )
      (libsource (lib "R-Semiconductors") (part "DAN217S3-0-T1-G"))
    )
    (comp (ref "D13")
      (value "T572006171251")
      (footprint "SOT323(SC-70)-R")
      (description "ITC 100V 215MA DAN217S3-0-T1-G CYSTE K")
      (fields
        (field (name "MFG") "CYSTECH")
        (field (name "MFG PART") "DAN217S3-0-T1-G")
        (field (name "CREATE NAME") "Nathan")
      )
      (libsource (lib "R-Semiconductors") (part "DAN217S3-0-T1-G"))
    )
    (comp (ref "D14")
      (value "T572006171251")
      (footprint "SOT323(SC-70)-R")
      (description "ITC 100V 215MA DAN217S3-0-T1-G CYSTE K")
      (fields
        (field (name "MFG") "CYSTECH")
        (field (name "MFG PART") "DAN217S3-0-T1-G")
        (field (name "CREATE NAME") "Nathan")
      )
      (libsource (lib "R-Semiconductors") (part "DAN217S3-0-T1-G"))
    )
    (comp (ref "D15")
      (value "T572006171251")
      (footprint "SOT323(SC-70)-R")
      (description "ITC 100V 215MA DAN217S3-0-T1-G CYSTE K")
      (fields
        (field (name "MFG") "CYSTECH")
        (field (name "MFG PART") "DAN217S3-0-T1-G")
        (field (name "CREATE NAME") "Nathan")
      )
      (libsource (lib "R-Semiconductors") (part "DAN217S3-0-T1-G"))
    )
    (comp (ref "D32")
      (value "T572006171251")
      (footprint "SOT323(SC-70)-R")
      (description "ITC 100V 215MA DAN217S3-0-T1-G CYSTE K")
      (fields
        (field (name "MFG") "CYSTECH")
        (field (name "MFG PART") "DAN217S3-0-T1-G")
        (field (name "CREATE NAME") "Nathan")
      )
      (libsource (lib "R-Semiconductors") (part "DAN217S3-0-T1-G"))
    )
    (comp (ref "D34")
      (value "T572006171251")
      (footprint "SOT323(SC-70)-R")
      (description "ITC 100V 215MA DAN217S3-0-T1-G CYSTE K")
      (fields
        (field (name "MFG") "CYSTECH")
        (field (name "MFG PART") "DAN217S3-0-T1-G")
        (field (name "CREATE NAME") "Nathan")
      )
      (libsource (lib "R-Semiconductors") (part "DAN217S3-0-T1-G"))
    )
    (comp (ref "J4")
      (value "T710200010000")
      (footprint "CONN XLR COMBO RCJ9FI-V-0")
      (description "COMBO JACK RCJ9FI-V-0 REAN K")
      (fields
        (field (name "MFG") "REAN")
        (field (name "MFG PART") "RCJ9FI-V-0")
        (field (name "CREATE_NAME") "Nathan")
      )
      (libsource (lib "C-Connector") (part "CONN XLR COMBO RCJ9FI-V-0"))
    )
    (comp (ref "J5")
      (value "T710200010000")
      (footprint "CONN XLR COMBO RCJ9FI-V-0")
      (description "COMBO JACK RCJ9FI-V-0 REAN K")
      (fields
        (field (name "MFG") "REAN")
        (field (name "MFG PART") "RCJ9FI-V-0")
        (field (name "CREATE_NAME") "Nathan")
      )
      (libsource (lib "C-Connector") (part "CONN XLR COMBO RCJ9FI-V-0"))
    )
    (comp (ref "JA11A")
      (value "T690300109200")
      (footprint "CONN 10P PH=1.5mm ST SMT ZH-10AT-JK")
      (description "SMT CONNECTOR 10PIN 1.5MM 90° K")
      (fields
        (field (name "MFG") "JINJIA")
        (field (name "MFG PART") "ZH-10AT-JK")
        (field (name "CREATE_NAME") "Nathan")
      )
      (libsource (lib "C-Connector") (part "CONN 10P PH=1.5MM ST SMT ZH-10AT-JK"))
    )
    (comp (ref "L7")
      (value "600R@100MHz")
      (footprint "L0603-RW")
      (description "BEAD 600 OHM 1A FBMA-11-160808-601A10T")
      (fields (field (name "MFG") "KING CORE") (field (name "MFG PART") "FBMA-11-160808-601A10T"))
      (libsource (lib "S-Inductor") (part "BEAD 0603 600R@100MHz FBMA-11-160808-601A10T"))
    )
    (comp (ref "L10")
      (value "600R@100MHz")
      (footprint "L0603-RW")
      (description "BEAD 600 OHM 1A FBMA-11-160808-601A10T")
      (fields (field (name "MFG") "KING CORE") (field (name "MFG PART") "FBMA-11-160808-601A10T"))
      (libsource (lib "S-Inductor") (part "BEAD 0603 600R@100MHz FBMA-11-160808-601A10T"))
    )
    (comp (ref "Q7")
      (value "T582003064899")
      (footprint "SOT-363")
      (description "PNP -40V HBP3906S6R SOT-36 CYSTEC K")
      (fields
        (field (name "MFG") "CYSTECH  (全宇昕科技)")
        (field (name "MFG PART") "HBP3906S6R")
        (field (name "CREATE_NAME") "Nathan")
      )
      (libsource (lib "R-Semiconductors") (part "HBP3906S6R"))
    )
    (comp (ref "Q8")
      (value "T582003064899")
      (footprint "SOT-363")
      (description "PNP -40V HBP3906S6R SOT-36 CYSTEC K")
      (fields
        (field (name "MFG") "CYSTECH  (全宇昕科技)")
        (field (name "MFG PART") "HBP3906S6R")
        (field (name "CREATE_NAME") "Nathan")
      )
      (libsource (lib "R-Semiconductors") (part "HBP3906S6R"))
    )
    (comp (ref "Q9")
      (value "T582003064899")
      (footprint "SOT-363")
      (description "PNP -40V HBP3906S6R SOT-36 CYSTEC K")
      (fields
        (field (name "MFG") "CYSTECH  (全宇昕科技)")
        (field (name "MFG PART") "HBP3906S6R")
        (field (name "CREATE_NAME") "Nathan")
      )
      (libsource (lib "R-Semiconductors") (part "HBP3906S6R"))
    )
    (comp (ref "Q11")
      (value "T582003064899")
      (footprint "SOT-363")
      (description "PNP -40V HBP3906S6R SOT-36 CYSTEC K")
      (fields
        (field (name "MFG") "CYSTECH  (全宇昕科技)")
        (field (name "MFG PART") "HBP3906S6R")
        (field (name "CREATE_NAME") "Nathan")
      )
      (libsource (lib "R-Semiconductors") (part "HBP3906S6R"))
    )
    (comp (ref "Q12")
      (value "T582003064899")
      (footprint "SOT-363")
      (description "PNP -40V HBP3906S6R SOT-36 CYSTEC K")
      (fields
        (field (name "MFG") "CYSTECH  (全宇昕科技)")
        (field (name "MFG PART") "HBP3906S6R")
        (field (name "CREATE_NAME") "Nathan")
      )
      (libsource (lib "R-Semiconductors") (part "HBP3906S6R"))
    )
    (comp (ref "Q13")
      (value "T582003064899")
      (footprint "SOT-363")
      (description "PNP -40V HBP3906S6R SOT-36 CYSTEC K")
      (fields
        (field (name "MFG") "CYSTECH  (全宇昕科技)")
        (field (name "MFG PART") "HBP3906S6R")
        (field (name "CREATE_NAME") "Nathan")
      )
      (libsource (lib "R-Semiconductors") (part "HBP3906S6R"))
    )
    (comp (ref "Q19")
      (value "RCC004413-0010")
      (footprint "SOT-363")
      (description "COMPOSOTE TRANSISTOR SOT-363 MMDT4413")
      (fields
        (field (name "MFG") "DIODES")
        (field (name "MFG_PART") "MMDT4413")
        (field (name "CREATE_NAME") "Nathan")
      )
      (libsource (lib "R-Semiconductors") (part "MMDT4413"))
    )
    (comp (ref "Q20")
      (value "RCC004413-0010")
      (footprint "SOT-363")
      (description "COMPOSOTE TRANSISTOR SOT-363 MMDT4413")
      (fields
        (field (name "MFG") "DIODES")
        (field (name "MFG_PART") "MMDT4413")
        (field (name "CREATE_NAME") "Nathan")
      )
      (libsource (lib "R-Semiconductors") (part "MMDT4413"))
    )
    (comp (ref "Q21")
      (value "RCC004413-0010")
      (footprint "SOT-363")
      (description "COMPOSOTE TRANSISTOR SOT-363 MMDT4413")
      (fields
        (field (name "MFG") "DIODES")
        (field (name "MFG_PART") "MMDT4413")
        (field (name "CREATE_NAME") "Nathan")
      )
      (libsource (lib "R-Semiconductors") (part "MMDT4413"))
    )
    (comp (ref "Q22")
      (value "RCC004413-0010")
      (footprint "SOT-363")
      (description "COMPOSOTE TRANSISTOR SOT-363 MMDT4413")
      (fields
        (field (name "MFG") "DIODES")
        (field (name "MFG_PART") "MMDT4413")
        (field (name "CREATE_NAME") "Nathan")
      )
      (libsource (lib "R-Semiconductors") (part "MMDT4413"))
    )
    (comp (ref "Q23")
      (value "RCC004413-0010")
      (footprint "SOT-363")
      (description "COMPOSOTE TRANSISTOR SOT-363 MMDT4413")
      (fields
        (field (name "MFG") "DIODES")
        (field (name "MFG_PART") "MMDT4413")
        (field (name "CREATE_NAME") "Nathan")
      )
      (libsource (lib "R-Semiconductors") (part "MMDT4413"))
    )
    (comp (ref "Q24")
      (value "RCC004413-0010")
      (footprint "SOT-363")
      (description "COMPOSOTE TRANSISTOR SOT-363 MMDT4413")
      (fields
        (field (name "MFG") "DIODES")
        (field (name "MFG_PART") "MMDT4413")
        (field (name "CREATE_NAME") "Nathan")
      )
      (libsource (lib "R-Semiconductors") (part "MMDT4413"))
    )
    (comp (ref "Q25")
      (value "RCC004413-0010")
      (footprint "SOT-363")
      (description "COMPOSOTE TRANSISTOR SOT-363 MMDT4413")
      (fields
        (field (name "MFG") "DIODES")
        (field (name "MFG_PART") "MMDT4413")
        (field (name "CREATE_NAME") "Nathan")
      )
      (libsource (lib "R-Semiconductors") (part "MMDT4413"))
    )
    (comp (ref "Q26")
      (value "RCC004413-0010")
      (footprint "SOT-363")
      (description "COMPOSOTE TRANSISTOR SOT-363 MMDT4413")
      (fields
        (field (name "MFG") "DIODES")
        (field (name "MFG_PART") "MMDT4413")
        (field (name "CREATE_NAME") "Nathan")
      )
      (libsource (lib "R-Semiconductors") (part "MMDT4413"))
    )
    (comp (ref "R1")
      (value "100R")
      (footprint "0603-RW")
      (description "GP CHIP RES. 100 OHM 1/10W 1% 0603")
      (fields (field (name "Comment") "QCF011030-1000"))
      (libsource (lib "Q-Resistors") (part "RES0603 1/10W 1% 100 OHM"))
    )
    (comp (ref "R2")
      (value "6.8K")
      (footprint "0603-RW")
      (description "GP CHIP RES. 6.8K OHM 1/10W 1% 0603")
      (fields (field (name "Comment") "QCF011030-6801"))
      (libsource (lib "Q-Resistors") (part "RES0603 1/10W 1% 6.8K OHM"))
    )
    (comp (ref "R3")
      (value "6.04K")
      (footprint "0603-RW")
      (description "CHIP 6.04K OHM 100PPM +-1% 0603 WALS L")
      (fields
        (field (name "POWER") "0.1W")
        (field (name "Comment") "T502604102399")
        (field (name "CREATE_NAME") "Tom")
      )
      (libsource (lib "Q-Resistors") (part "RES0603 1/10W 1% 6.04K OHM"))
    )
    (comp (ref "R4")
      (value "10K")
      (footprint "0603-RW")
      (description "GP CHIP RES. 10K OHM 1/10W 1% 0603")
      (fields (field (name "Comment") "QCF011030-1002"))
      (libsource (lib "Q-Resistors") (part "RES0603 1/10W 1% 10K OHM"))
    )
    (comp (ref "R5")
      (value "1M")
      (footprint "0603-RW")
      (description "GP CHIP RES. 1M OHM 1/10W 1% 0603")
      (fields (field (name "Comment") "QCF011030-1004"))
      (libsource (lib "Q-Resistors") (part "RES0603 1/10W 1% 1M OHM"))
    )
    (comp (ref "R6")
      (value "10M")
      (footprint "0603-RW")
      (description "CHIP RES. 10M OHM 1/10W 1% 0603")
      (fields (field (name "Comment") "QCF011030-1005"))
      (libsource (lib "Q-Resistors") (part "RES0603 1/10W 1% 10M OHM"))
    )
    (comp (ref "R7")
      (value "1M")
      (footprint "0603-RW")
      (description "GP CHIP RES. 1M OHM 1/10W 1% 0603")
      (fields (field (name "Comment") "QCF011030-1004"))
      (libsource (lib "Q-Resistors") (part "RES0603 1/10W 1% 1M OHM"))
    )
    (comp (ref "R8")
      (value "DNI")
      (footprint "0603-RW")
      (description "CHIP RES 1.1K OHM 1% 1/10W 0603")
      (fields (field (name "Comment") "QCF011030-1101") (field (name "CREATE_NAME") "GordonL@Deftronics"))
      (libsource (lib "Q-Resistors") (part "RES0603 1/10W 1% 1.1K OHM"))
    )
    (comp (ref "R9")
      (value "10K")
      (footprint "0603-RW")
      (description "GP CHIP RES. 10K OHM 1/10W 1% 0603")
      (fields (field (name "Comment") "QCF011030-1002"))
      (libsource (lib "Q-Resistors") (part "RES0603 1/10W 1% 10K OHM"))
    )
    (comp (ref "R10")
      (value "330R")
      (footprint "0603-RW")
      (description "CHIP RES. 330 OHM 1/10W 1% 0603")
      (fields (field (name "Comment") "QCF011031-3300"))
      (libsource (lib "Q-Resistors") (part "RES0603 1/10W 1% 330 OHM"))
    )
    (comp (ref "R13")
      (value "1M")
      (footprint "0603-RW")
      (description "GP CHIP RES. 1M OHM 1/10W 1% 0603")
      (fields (field (name "Comment") "QCF011030-1004"))
      (libsource (lib "Q-Resistors") (part "RES0603 1/10W 1% 1M OHM"))
    )
    (comp (ref "R16")
      (value "10M")
      (footprint "0603-RW")
      (description "CHIP RES. 10M OHM 1/10W 1% 0603")
      (fields (field (name "Comment") "QCF011030-1005"))
      (libsource (lib "Q-Resistors") (part "RES0603 1/10W 1% 10M OHM"))
    )
    (comp (ref "R17")
      (value "6.8K")
      (footprint "0603-RW")
      (description "GP CHIP RES. 6.8K OHM 1/10W 1% 0603")
      (fields (field (name "Comment") "QCF011030-6801"))
      (libsource (lib "Q-Resistors") (part "RES0603 1/10W 1% 6.8K OHM"))
    )
    (comp (ref "R18")
      (value "100R")
      (footprint "0603-RW")
      (description "GP CHIP RES. 100 OHM 1/10W 1% 0603")
      (fields (field (name "Comment") "QCF011030-1000"))
      (libsource (lib "Q-Resistors") (part "RES0603 1/10W 1% 100 OHM"))
    )
    (comp (ref "R19")
      (value "100R")
      (footprint "0603-RW")
      (description "GP CHIP RES. 100 OHM 1/10W 1% 0603")
      (fields (field (name "Comment") "QCF011030-1000"))
      (libsource (lib "Q-Resistors") (part "RES0603 1/10W 1% 100 OHM"))
    )
    (comp (ref "R21")
      (value "10K")
      (footprint "0603-RW")
      (description "GP CHIP RES. 10K OHM 1/10W 1% 0603")
      (fields (field (name "Comment") "QCF011030-1002"))
      (libsource (lib "Q-Resistors") (part "RES0603 1/10W 1% 10K OHM"))
    )
    (comp (ref "R22")
      (value "10R")
      (footprint "0603-RW")
      (description "GP CHIP RES. 10 OHM 1/10W 1% 0603")
      (fields (field (name "Comment") "QCF011030-1009"))
      (libsource (lib "Q-Resistors") (part "RES0603 1/10W 1% 10 OHM"))
    )
    (comp (ref "R24")
      (value "10K")
      (footprint "0603-RW")
      (description "GP CHIP RES. 10K OHM 1/10W 1% 0603")
      (fields (field (name "Comment") "QCF011030-1002"))
      (libsource (lib "Q-Resistors") (part "RES0603 1/10W 1% 10K OHM"))
    )
    (comp (ref "R25")
      (value "330R")
      (footprint "0603-RW")
      (description "CHIP RES. 330 OHM 1/10W 1% 0603")
      (fields (field (name "Comment") "QCF011031-3300"))
      (libsource (lib "Q-Resistors") (part "RES0603 1/10W 1% 330 OHM"))
    )
    (comp (ref "R26")
      (value "5K9")
      (footprint "0603-RW")
      (description "CHIP 5.9K OHM  100PPM +-1% 0603 WALS L")
      (fields
        (field (name "POWER") "~{1}10W")
        (field (name "MFG") "WALSIN (華新)")
        (field (name "CREAT_NAME") "Nathan")
      )
      (libsource (lib "Q-Resistors") (part "RES0603 1/10W 1% 5.9K OHM_WALSIN"))
    )
    (comp (ref "R31")
      (value "100K")
      (footprint "0402-RW")
      (description "CHIP RES 100K OHM 1/16W 1% 0402")
      (fields (field (name "MFG") "WALSIN") (field (name "Comment") "QCF161240-1003"))
      (libsource (lib "Q-Resistors") (part "RES0402 1/16W 1% 100K OHM-QCF161240-1003"))
    )
    (comp (ref "R32")
      (value "4K42")
      (footprint "0603-RW")
      (description "CHIP 4.42K OHM 100PPM +-1% 0603 WALS L")
      (fields
        (field (name "MFG") "WALSIN (華新)")
        (field (name "Comment") "T502442102399")
        (field (name "CREAT_NAME") "Nathan")
      )
      (libsource (lib "Q-Resistors") (part "RES0603 1/10W 1% 4.42K OHM_WALSIN"))
    )
    (comp (ref "R33")
      (value "4K42")
      (footprint "0603-RW")
      (description "CHIP 4.42K OHM 100PPM +-1% 0603 WALS L")
      (fields
        (field (name "MFG") "WALSIN (華新)")
        (field (name "Comment") "T502442102399")
        (field (name "CREAT_NAME") "Nathan")
      )
      (libsource (lib "Q-Resistors") (part "RES0603 1/10W 1% 4.42K OHM_WALSIN"))
    )
    (comp (ref "R34")
      (value "4K42")
      (footprint "0603-RW")
      (description "CHIP 4.42K OHM 100PPM +-1% 0603 WALS L")
      (fields
        (field (name "MFG") "WALSIN (華新)")
        (field (name "Comment") "T502442102399")
        (field (name "CREAT_NAME") "Nathan")
      )
      (libsource (lib "Q-Resistors") (part "RES0603 1/10W 1% 4.42K OHM_WALSIN"))
    )
    (comp (ref "R36")
      (value "DNI")
      (footprint "0603-RW")
      (description "CHIP RES 1.1K OHM 1% 1/10W 0603")
      (fields (field (name "Comment") "QCF011030-1101") (field (name "CREATE_NAME") "GordonL@Deftronics"))
      (libsource (lib "Q-Resistors") (part "RES0603 1/10W 1% 1.1K OHM"))
    )
    (comp (ref "R37")
      (value "1.5K")
      (footprint "0603-RW")
      (description "GP CHIP RES. 1.5K OHM 1/10W 1% 0603")
      (fields (field (name "Comment") "QCF011030-1501"))
      (libsource (lib "Q-Resistors") (part "RES0603 1/10W 1% 1.5K OHM"))
    )
    (comp (ref "R41")
      (value "6.04K")
      (footprint "0603-RW")
      (description "CHIP 6.04K OHM 100PPM +-1% 0603 WALS L")
      (fields
        (field (name "POWER") "0.1W")
        (field (name "Comment") "T502604102399")
        (field (name "CREATE_NAME") "Tom")
      )
      (libsource (lib "Q-Resistors") (part "RES0603 1/10W 1% 6.04K OHM"))
    )
    (comp (ref "R42")
      (value "4K42")
      (footprint "0603-RW")
      (description "CHIP 4.42K OHM 100PPM +-1% 0603 WALS L")
      (fields
        (field (name "MFG") "WALSIN (華新)")
        (field (name "Comment") "T502442102399")
        (field (name "CREAT_NAME") "Nathan")
      )
      (libsource (lib "Q-Resistors") (part "RES0603 1/10W 1% 4.42K OHM_WALSIN"))
    )
    (comp (ref "R44")
      (value "5K9")
      (footprint "0603-RW")
      (description "CHIP 5.9K OHM  100PPM +-1% 0603 WALS L")
      (fields
        (field (name "POWER") "~{1}10W")
        (field (name "MFG") "WALSIN (華新)")
        (field (name "CREAT_NAME") "Nathan")
      )
      (libsource (lib "Q-Resistors") (part "RES0603 1/10W 1% 5.9K OHM_WALSIN"))
    )
    (comp (ref "R45")
      (value "1M")
      (footprint "0603-RW")
      (description "GP CHIP RES. 1M OHM 1/10W 1% 0603")
      (fields (field (name "Comment") "QCF011030-1004"))
      (libsource (lib "Q-Resistors") (part "RES0603 1/10W 1% 1M OHM"))
    )
    (comp (ref "R48")
      (value "100K")
      (footprint "0402-RW")
      (description "CHIP RES 100K OHM 1/16W 1% 0402")
      (fields (field (name "MFG") "WALSIN") (field (name "Comment") "QCF161240-1003"))
      (libsource (lib "Q-Resistors") (part "RES0402 1/16W 1% 100K OHM-QCF161240-1003"))
    )
    (comp (ref "R50")
      (value "100R")
      (footprint "0603-RW")
      (description "GP CHIP RES. 100 OHM 1/10W 1% 0603")
      (fields (field (name "Comment") "QCF011030-1000"))
      (libsource (lib "Q-Resistors") (part "RES0603 1/10W 1% 100 OHM"))
    )
    (comp (ref "R51")
      (value "10K")
      (footprint "0603-RW")
      (description "GP CHIP RES. 10K OHM 1/10W 1% 0603")
      (fields (field (name "Comment") "QCF011030-1002"))
      (libsource (lib "Q-Resistors") (part "RES0603 1/10W 1% 10K OHM"))
    )
    (comp (ref "R52")
      (value "10K")
      (footprint "0603-RW")
      (description "GP CHIP RES. 10K OHM 1/10W 1% 0603")
      (fields (field (name "Comment") "QCF011030-1002"))
      (libsource (lib "Q-Resistors") (part "RES0603 1/10W 1% 10K OHM"))
    )
    (comp (ref "R53")
      (value "10R")
      (footprint "0603-RW")
      (description "GP CHIP RES. 10 OHM 1/10W 1% 0603")
      (fields (field (name "Comment") "QCF011030-1009"))
      (libsource (lib "Q-Resistors") (part "RES0603 1/10W 1% 10 OHM"))
    )
    (comp (ref "R110")
      (value "1M")
      (footprint "0603-RW")
      (description "GP CHIP RES. 1M OHM 1/10W 1% 0603")
      (fields (field (name "Comment") "QCF011030-1004"))
      (libsource (lib "Q-Resistors") (part "RES0603 1/10W 1% 1M OHM"))
    )
    (comp (ref "R113")
      (value "330R")
      (footprint "0603-RW")
      (description "CHIP RES. 330 OHM 1/10W 1% 0603")
      (fields (field (name "Comment") "QCF011031-3300"))
      (libsource (lib "Q-Resistors") (part "RES0603 1/10W 1% 330 OHM"))
    )
    (comp (ref "R122")
      (value "49R9")
      (footprint "0402-RW")
      (description "CHIP RES 49.9 OMH 1/16W 1% 0402")
      (fields (field (name "Comment") "QCF161241-4999") (field (name "CREATE_NAME") "GordonL@Deftronics"))
      (libsource (lib "Q-Resistors") (part "RES0402 1/16W 1% 49.9R OHM"))
    )
    (comp (ref "R131")
      (value "6.04K")
      (footprint "0603-RW")
      (description "CHIP 6.04K OHM 100PPM +-1% 0603 WALS L")
      (fields
        (field (name "POWER") "0.1W")
        (field (name "Comment") "T502604102399")
        (field (name "CREATE_NAME") "Tom")
      )
      (libsource (lib "Q-Resistors") (part "RES0603 1/10W 1% 6.04K OHM"))
    )
    (comp (ref "R133")
      (value "1M")
      (footprint "0603-RW")
      (description "GP CHIP RES. 1M OHM 1/10W 1% 0603")
      (fields (field (name "Comment") "QCF011030-1004"))
      (libsource (lib "Q-Resistors") (part "RES0603 1/10W 1% 1M OHM"))
    )
    (comp (ref "R135")
      (value "10M")
      (footprint "0603-RW")
      (description "CHIP RES. 10M OHM 1/10W 1% 0603")
      (fields (field (name "Comment") "QCF011030-1005"))
      (libsource (lib "Q-Resistors") (part "RES0603 1/10W 1% 10M OHM"))
    )
    (comp (ref "R142")
      (value "1M")
      (footprint "0603-RW")
      (description "GP CHIP RES. 1M OHM 1/10W 1% 0603")
      (fields (field (name "Comment") "QCF011030-1004"))
      (libsource (lib "Q-Resistors") (part "RES0603 1/10W 1% 1M OHM"))
    )
    (comp (ref "R144")
      (value "1M")
      (footprint "0603-RW")
      (description "GP CHIP RES. 1M OHM 1/10W 1% 0603")
      (fields (field (name "Comment") "QCF011030-1004"))
      (libsource (lib "Q-Resistors") (part "RES0603 1/10W 1% 1M OHM"))
    )
    (comp (ref "R146")
      (value "1M")
      (footprint "0603-RW")
      (description "GP CHIP RES. 1M OHM 1/10W 1% 0603")
      (fields (field (name "Comment") "QCF011030-1004"))
      (libsource (lib "Q-Resistors") (part "RES0603 1/10W 1% 1M OHM"))
    )
    (comp (ref "R148")
      (value "1M")
      (footprint "0603-RW")
      (description "GP CHIP RES. 1M OHM 1/10W 1% 0603")
      (fields (field (name "Comment") "QCF011030-1004"))
      (libsource (lib "Q-Resistors") (part "RES0603 1/10W 1% 1M OHM"))
    )
    (comp (ref "R149")
      (value "330R")
      (footprint "0603-RW")
      (description "CHIP RES. 330 OHM 1/10W 1% 0603")
      (fields (field (name "Comment") "QCF011031-3300"))
      (libsource (lib "Q-Resistors") (part "RES0603 1/10W 1% 330 OHM"))
    )
    (comp (ref "R150")
      (value "10M")
      (footprint "0603-RW")
      (description "CHIP RES. 10M OHM 1/10W 1% 0603")
      (fields (field (name "Comment") "QCF011030-1005"))
      (libsource (lib "Q-Resistors") (part "RES0603 1/10W 1% 10M OHM"))
    )
    (comp (ref "R152")
      (value "6.8K")
      (footprint "0603-RW")
      (description "GP CHIP RES. 6.8K OHM 1/10W 1% 0603")
      (fields (field (name "Comment") "QCF011030-6801"))
      (libsource (lib "Q-Resistors") (part "RES0603 1/10W 1% 6.8K OHM"))
    )
    (comp (ref "R153")
      (value "100R")
      (footprint "0603-RW")
      (description "GP CHIP RES. 100 OHM 1/10W 1% 0603")
      (fields (field (name "Comment") "QCF011030-1000"))
      (libsource (lib "Q-Resistors") (part "RES0603 1/10W 1% 100 OHM"))
    )
    (comp (ref "R154")
      (value "100R")
      (footprint "0603-RW")
      (description "GP CHIP RES. 100 OHM 1/10W 1% 0603")
      (fields (field (name "Comment") "QCF011030-1000"))
      (libsource (lib "Q-Resistors") (part "RES0603 1/10W 1% 100 OHM"))
    )
    (comp (ref "R156")
      (value "10R")
      (footprint "0603-RW")
      (description "GP CHIP RES. 10 OHM 1/10W 1% 0603")
      (fields (field (name "Comment") "QCF011030-1009"))
      (libsource (lib "Q-Resistors") (part "RES0603 1/10W 1% 10 OHM"))
    )
    (comp (ref "R162")
      (value "100K")
      (footprint "0402-RW")
      (description "CHIP RES 100K OHM 1/16W 1% 0402")
      (fields (field (name "MFG") "WALSIN") (field (name "Comment") "QCF161240-1003"))
      (libsource (lib "Q-Resistors") (part "RES0402 1/16W 1% 100K OHM-QCF161240-1003"))
    )
    (comp (ref "R166")
      (value "49R9")
      (footprint "0402-RW")
      (description "CHIP RES 49.9 OMH 1/16W 1% 0402")
      (fields (field (name "Comment") "QCF161241-4999") (field (name "CREATE_NAME") "GordonL@Deftronics"))
      (libsource (lib "Q-Resistors") (part "RES0402 1/16W 1% 49.9R OHM"))
    )
    (comp (ref "R172")
      (value "1.5K")
      (footprint "0603-RW")
      (description "GP CHIP RES. 1.5K OHM 1/10W 1% 0603")
      (fields (field (name "Comment") "QCF011030-1501"))
      (libsource (lib "Q-Resistors") (part "RES0603 1/10W 1% 1.5K OHM"))
    )
    (comp (ref "R175")
      (value "6.04K")
      (footprint "0603-RW")
      (description "CHIP 6.04K OHM 100PPM +-1% 0603 WALS L")
      (fields
        (field (name "POWER") "0.1W")
        (field (name "Comment") "T502604102399")
        (field (name "CREATE_NAME") "Tom")
      )
      (libsource (lib "Q-Resistors") (part "RES0603 1/10W 1% 6.04K OHM"))
    )
    (comp (ref "R178")
      (value "1M")
      (footprint "0603-RW")
      (description "GP CHIP RES. 1M OHM 1/10W 1% 0603")
      (fields (field (name "Comment") "QCF011030-1004"))
      (libsource (lib "Q-Resistors") (part "RES0603 1/10W 1% 1M OHM"))
    )
    (comp (ref "R182")
      (value "100K")
      (footprint "0402-RW")
      (description "CHIP RES 100K OHM 1/16W 1% 0402")
      (fields (field (name "MFG") "WALSIN") (field (name "Comment") "QCF161240-1003"))
      (libsource (lib "Q-Resistors") (part "RES0402 1/16W 1% 100K OHM-QCF161240-1003"))
    )
    (comp (ref "R186")
      (value "100R")
      (footprint "0603-RW")
      (description "GP CHIP RES. 100 OHM 1/10W 1% 0603")
      (fields (field (name "Comment") "QCF011030-1000"))
      (libsource (lib "Q-Resistors") (part "RES0603 1/10W 1% 100 OHM"))
    )
    (comp (ref "R188")
      (value "10R")
      (footprint "0603-RW")
      (description "GP CHIP RES. 10 OHM 1/10W 1% 0603")
      (fields (field (name "Comment") "QCF011030-1009"))
      (libsource (lib "Q-Resistors") (part "RES0603 1/10W 1% 10 OHM"))
    )
    (comp (ref "R189")
      (value "13K7")
      (footprint "0603-RW")
      (description "CHIP 13.7K OHM 100PPM +-1% 0603 WALS L")
      (fields
        (field (name "MFG") "WALSIN (華新)")
        (field (name "Comment") "T502137202399")
        (field (name "CREAT_NAME") "Nathan")
      )
      (libsource (lib "Q-Resistors") (part "RES0603 1/10W 1% 13.7K OHM_WALSIN"))
    )
    (comp (ref "R191")
      (value "DNI")
      (footprint "0603-RW")
      (description "CHIP RES 56K OHM 1/10W 1% 0603")
      (fields (field (name "Comment") "QCF011030-5602"))
      (libsource (lib "Q-Resistors") (part "RES0603 1/10W 1% 56K OHM"))
    )
    (comp (ref "R192")
      (value "NC")
      (footprint "0603-RW")
      (description "CHIP RES 1.1K OHM 1% 1/10W 0603")
      (fields (field (name "Comment") "QCF011030-1101") (field (name "CREATE_NAME") "GordonL@Deftronics"))
      (libsource (lib "Q-Resistors") (part "RES0603 1/10W 1% 1.1K OHM"))
    )
    (comp (ref "R194")
      (value "0R")
      (footprint "0603-RW")
      (description "CHIP 0 OHM 0 OHM 0 OHM 0603 WALSIN L")
      (fields (field (name "MFG PART") "WR06X000PTL") (field (name "MFG") "WALSIN (èAD?)"))
      (libsource (lib "Q-Resistors") (part "RES0603 1/10W 0 OHM_WALSIN"))
    )
    (comp (ref "R197")
      (value "13K7")
      (footprint "0603-RW")
      (description "CHIP 13.7K OHM 100PPM +-1% 0603 WALS L")
      (fields
        (field (name "MFG") "WALSIN (華新)")
        (field (name "Comment") "T502137202399")
        (field (name "CREAT_NAME") "Nathan")
      )
      (libsource (lib "Q-Resistors") (part "RES0603 1/10W 1% 13.7K OHM_WALSIN"))
    )
    (comp (ref "R198")
      (value "1K")
      (footprint "0402-RW")
      (description "CHIP RES 1K OHM 1/16W 1% 0402")
      (fields (field (name "MFG") "WALSIN") (field (name "Comment") "QCF161240-1001"))
      (libsource (lib "Q-Resistors") (part "RES0402 1/16W 1% 1K OHM"))
    )
    (comp (ref "R200")
      (value "1M")
      (footprint "0603-RW")
      (description "GP CHIP RES. 1M OHM 1/10W 1% 0603")
      (fields (field (name "Comment") "QCF011030-1004"))
      (libsource (lib "Q-Resistors") (part "RES0603 1/10W 1% 1M OHM"))
    )
    (comp (ref "R202")
      (value "13K7")
      (footprint "0603-RW")
      (description "CHIP 13.7K OHM 100PPM +-1% 0603 WALS L")
      (fields
        (field (name "MFG") "WALSIN (華新)")
        (field (name "Comment") "T502137202399")
        (field (name "CREAT_NAME") "Nathan")
      )
      (libsource (lib "Q-Resistors") (part "RES0603 1/10W 1% 13.7K OHM_WALSIN"))
    )
    (comp (ref "R203")
      (value "DNI")
      (footprint "0603-RW")
      (description "CHIP RES 56K OHM 1/10W 1% 0603")
      (fields (field (name "Comment") "QCF011030-5602"))
      (libsource (lib "Q-Resistors") (part "RES0603 1/10W 1% 56K OHM"))
    )
    (comp (ref "R205")
      (value "NC")
      (footprint "0603-RW")
      (description "CHIP RES 1.1K OHM 1% 1/10W 0603")
      (fields (field (name "Comment") "QCF011030-1101") (field (name "CREATE_NAME") "GordonL@Deftronics"))
      (libsource (lib "Q-Resistors") (part "RES0603 1/10W 1% 1.1K OHM"))
    )
    (comp (ref "R206")
      (value "0R")
      (footprint "0603-RW")
      (description "CHIP 0 OHM 0 OHM 0 OHM 0603 WALSIN L")
      (fields (field (name "MFG PART") "WR06X000PTL") (field (name "MFG") "WALSIN (èAD?)"))
      (libsource (lib "Q-Resistors") (part "RES0603 1/10W 0 OHM_WALSIN"))
    )
    (comp (ref "R207")
      (value "13K7")
      (footprint "0603-RW")
      (description "CHIP 13.7K OHM 100PPM +-1% 0603 WALS L")
      (fields
        (field (name "MFG") "WALSIN (華新)")
        (field (name "Comment") "T502137202399")
        (field (name "CREAT_NAME") "Nathan")
      )
      (libsource (lib "Q-Resistors") (part "RES0603 1/10W 1% 13.7K OHM_WALSIN"))
    )
    (comp (ref "R211")
      (value "1M")
      (footprint "0603-RW")
      (description "GP CHIP RES. 1M OHM 1/10W 1% 0603")
      (fields (field (name "Comment") "QCF011030-1004"))
      (libsource (lib "Q-Resistors") (part "RES0603 1/10W 1% 1M OHM"))
    )
    (comp (ref "R215")
      (value "13K7")
      (footprint "0603-RW")
      (description "CHIP 13.7K OHM 100PPM +-1% 0603 WALS L")
      (fields
        (field (name "MFG") "WALSIN (華新)")
        (field (name "Comment") "T502137202399")
        (field (name "CREAT_NAME") "Nathan")
      )
      (libsource (lib "Q-Resistors") (part "RES0603 1/10W 1% 13.7K OHM_WALSIN"))
    )
    (comp (ref "R216")
      (value "DNI")
      (footprint "0603-RW")
      (description "CHIP RES 56K OHM 1/10W 1% 0603")
      (fields (field (name "Comment") "QCF011030-5602"))
      (libsource (lib "Q-Resistors") (part "RES0603 1/10W 1% 56K OHM"))
    )
    (comp (ref "R217")
      (value "NC")
      (footprint "0603-RW")
      (description "CHIP RES 1.1K OHM 1% 1/10W 0603")
      (fields (field (name "Comment") "QCF011030-1101") (field (name "CREATE_NAME") "GordonL@Deftronics"))
      (libsource (lib "Q-Resistors") (part "RES0603 1/10W 1% 1.1K OHM"))
    )
    (comp (ref "R218")
      (value "0R")
      (footprint "0603-RW")
      (description "CHIP 0 OHM 0 OHM 0 OHM 0603 WALSIN L")
      (fields (field (name "MFG PART") "WR06X000PTL") (field (name "MFG") "WALSIN (èAD?)"))
      (libsource (lib "Q-Resistors") (part "RES0603 1/10W 0 OHM_WALSIN"))
    )
    (comp (ref "R219")
      (value "13K7")
      (footprint "0603-RW")
      (description "CHIP 13.7K OHM 100PPM +-1% 0603 WALS L")
      (fields
        (field (name "MFG") "WALSIN (華新)")
        (field (name "Comment") "T502137202399")
        (field (name "CREAT_NAME") "Nathan")
      )
      (libsource (lib "Q-Resistors") (part "RES0603 1/10W 1% 13.7K OHM_WALSIN"))
    )
    (comp (ref "R220")
      (value "910R")
      (footprint "0402-RW")
      (description "CHIP 910 OHM 100PPM +-1% 0402 WALS L")
      (fields
        (field (name "MFG PART") "WR04X9100FTL")
        (field (name "MFG") "WALSIN (華新)")
        (field (name "CREATE_NAME") "Nathan")
      )
      (libsource (lib "Q-Resistors") (part "RES0402 1/16W 1% 910 OMH_100PPM_WALSIN"))
    )
    (comp (ref "R221")
      (value "1M")
      (footprint "0603-RW")
      (description "GP CHIP RES. 1M OHM 1/10W 1% 0603")
      (fields (field (name "Comment") "QCF011030-1004"))
      (libsource (lib "Q-Resistors") (part "RES0603 1/10W 1% 1M OHM"))
    )
    (comp (ref "R222")
      (value "13K7")
      (footprint "0603-RW")
      (description "CHIP 13.7K OHM 100PPM +-1% 0603 WALS L")
      (fields
        (field (name "MFG") "WALSIN (華新)")
        (field (name "Comment") "T502137202399")
        (field (name "CREAT_NAME") "Nathan")
      )
      (libsource (lib "Q-Resistors") (part "RES0603 1/10W 1% 13.7K OHM_WALSIN"))
    )
    (comp (ref "R223")
      (value "DNI")
      (footprint "0603-RW")
      (description "CHIP RES 56K OHM 1/10W 1% 0603")
      (fields (field (name "Comment") "QCF011030-5602"))
      (libsource (lib "Q-Resistors") (part "RES0603 1/10W 1% 56K OHM"))
    )
    (comp (ref "R224")
      (value "NC")
      (footprint "0603-RW")
      (description "CHIP RES 1.1K OHM 1% 1/10W 0603")
      (fields (field (name "Comment") "QCF011030-1101") (field (name "CREATE_NAME") "GordonL@Deftronics"))
      (libsource (lib "Q-Resistors") (part "RES0603 1/10W 1% 1.1K OHM"))
    )
    (comp (ref "R236")
      (value "910R")
      (footprint "0402-RW")
      (description "CHIP 910 OHM 100PPM +-1% 0402 WALS L")
      (fields
        (field (name "MFG PART") "WR04X9100FTL")
        (field (name "MFG") "WALSIN (華新)")
        (field (name "CREATE_NAME") "Nathan")
      )
      (libsource (lib "Q-Resistors") (part "RES0402 1/16W 1% 910 OMH_100PPM_WALSIN"))
    )
    (comp (ref "R237")
      (value "4.02K")
      (footprint "0402-RW")
      (description "CHIP RES 4.02K OHM 1% 1/16W 0402 华新")
      (fields (field (name "Comment") "QCF161240-4021") (field (name "CREATE_NAME") "GordonL@Deftronics"))
      (libsource (lib "Q-Resistors") (part "RES0402 1/16W 1% 4.02K OHM"))
    )
    (comp (ref "R238")
      (value "0R")
      (footprint "0603-RW")
      (description "CHIP 0 OHM 0 OHM 0 OHM 0603 WALSIN L")
      (fields (field (name "MFG PART") "WR06X000PTL") (field (name "MFG") "WALSIN (èAD?)"))
      (libsource (lib "Q-Resistors") (part "RES0603 1/10W 0 OHM_WALSIN"))
    )
    (comp (ref "R239")
      (value "1K")
      (footprint "0402-RW")
      (description "CHIP RES 1K OHM 1/16W 1% 0402")
      (fields (field (name "MFG") "WALSIN") (field (name "Comment") "QCF161240-1001"))
      (libsource (lib "Q-Resistors") (part "RES0402 1/16W 1% 1K OHM"))
    )
    (comp (ref "R248")
      (value "13K7")
      (footprint "0603-RW")
      (description "CHIP 13.7K OHM 100PPM +-1% 0603 WALS L")
      (fields
        (field (name "MFG") "WALSIN (華新)")
        (field (name "Comment") "T502137202399")
        (field (name "CREAT_NAME") "Nathan")
      )
      (libsource (lib "Q-Resistors") (part "RES0603 1/10W 1% 13.7K OHM_WALSIN"))
    )
    (comp (ref "R249")
      (value "4.02K")
      (footprint "0402-RW")
      (description "CHIP RES 4.02K OHM 1% 1/16W 0402 华新")
      (fields (field (name "Comment") "QCF161240-4021") (field (name "CREATE_NAME") "GordonL@Deftronics"))
      (libsource (lib "Q-Resistors") (part "RES0402 1/16W 1% 4.02K OHM"))
    )
    (comp (ref "R252")
      (value "1K")
      (footprint "0402-RW")
      (description "CHIP RES 1K OHM 1/16W 1% 0402")
      (fields (field (name "MFG") "WALSIN") (field (name "Comment") "QCF161240-1001"))
      (libsource (lib "Q-Resistors") (part "RES0402 1/16W 1% 1K OHM"))
    )
    (comp (ref "R253")
      (value "910R")
      (footprint "0402-RW")
      (description "CHIP 910 OHM 100PPM +-1% 0402 WALS L")
      (fields
        (field (name "MFG PART") "WR04X9100FTL")
        (field (name "MFG") "WALSIN (華新)")
        (field (name "CREATE_NAME") "Nathan")
      )
      (libsource (lib "Q-Resistors") (part "RES0402 1/16W 1% 910 OMH_100PPM_WALSIN"))
    )
    (comp (ref "R264")
      (value "910R")
      (footprint "0402-RW")
      (description "CHIP 910 OHM 100PPM +-1% 0402 WALS L")
      (fields
        (field (name "MFG PART") "WR04X9100FTL")
        (field (name "MFG") "WALSIN (華新)")
        (field (name "CREATE_NAME") "Nathan")
      )
      (libsource (lib "Q-Resistors") (part "RES0402 1/16W 1% 910 OMH_100PPM_WALSIN"))
    )
    (comp (ref "R265")
      (value "4.02K")
      (footprint "0402-RW")
      (description "CHIP RES 4.02K OHM 1% 1/16W 0402 华新")
      (fields (field (name "Comment") "QCF161240-4021") (field (name "CREATE_NAME") "GordonL@Deftronics"))
      (libsource (lib "Q-Resistors") (part "RES0402 1/16W 1% 4.02K OHM"))
    )
    (comp (ref "R269")
      (value "1K")
      (footprint "0402-RW")
      (description "CHIP RES 1K OHM 1/16W 1% 0402")
      (fields (field (name "MFG") "WALSIN") (field (name "Comment") "QCF161240-1001"))
      (libsource (lib "Q-Resistors") (part "RES0402 1/16W 1% 1K OHM"))
    )
    (comp (ref "R271")
      (value "4.02K")
      (footprint "0402-RW")
      (description "CHIP RES 4.02K OHM 1% 1/16W 0402 华新")
      (fields (field (name "Comment") "QCF161240-4021") (field (name "CREATE_NAME") "GordonL@Deftronics"))
      (libsource (lib "Q-Resistors") (part "RES0402 1/16W 1% 4.02K OHM"))
    )
    (comp (ref "R274")
      (value "1K")
      (footprint "0402-RW")
      (description "CHIP RES 1K OHM 1/16W 1% 0402")
      (fields (field (name "MFG") "WALSIN") (field (name "Comment") "QCF161240-1001"))
      (libsource (lib "Q-Resistors") (part "RES0402 1/16W 1% 1K OHM"))
    )
    (comp (ref "R284")
      (value "5K9")
      (footprint "0603-RW")
      (description "CHIP 5.9K OHM  100PPM +-1% 0603 WALS L")
      (fields
        (field (name "POWER") "~{1}10W")
        (field (name "MFG") "WALSIN (華新)")
        (field (name "CREAT_NAME") "Nathan")
      )
      (libsource (lib "Q-Resistors") (part "RES0603 1/10W 1% 5.9K OHM_WALSIN"))
    )
    (comp (ref "R286")
      (value "4K42")
      (footprint "0603-RW")
      (description "CHIP 4.42K OHM 100PPM +-1% 0603 WALS L")
      (fields
        (field (name "MFG") "WALSIN (華新)")
        (field (name "Comment") "T502442102399")
        (field (name "CREAT_NAME") "Nathan")
      )
      (libsource (lib "Q-Resistors") (part "RES0603 1/10W 1% 4.42K OHM_WALSIN"))
    )
    (comp (ref "R290")
      (value "4K42")
      (footprint "0603-RW")
      (description "CHIP 4.42K OHM 100PPM +-1% 0603 WALS L")
      (fields
        (field (name "MFG") "WALSIN (華新)")
        (field (name "Comment") "T502442102399")
        (field (name "CREAT_NAME") "Nathan")
      )
      (libsource (lib "Q-Resistors") (part "RES0603 1/10W 1% 4.42K OHM_WALSIN"))
    )
    (comp (ref "R291")
      (value "5K9")
      (footprint "0603-RW")
      (description "CHIP 5.9K OHM  100PPM +-1% 0603 WALS L")
      (fields
        (field (name "POWER") "~{1}10W")
        (field (name "MFG") "WALSIN (華新)")
        (field (name "CREAT_NAME") "Nathan")
      )
      (libsource (lib "Q-Resistors") (part "RES0603 1/10W 1% 5.9K OHM_WALSIN"))
    )
    (comp (ref "R292")
      (value "5K9")
      (footprint "0603-RW")
      (description "CHIP 5.9K OHM  100PPM +-1% 0603 WALS L")
      (fields
        (field (name "POWER") "~{1}10W")
        (field (name "MFG") "WALSIN (華新)")
        (field (name "CREAT_NAME") "Nathan")
      )
      (libsource (lib "Q-Resistors") (part "RES0603 1/10W 1% 5.9K OHM_WALSIN"))
    )
    (comp (ref "R294")
      (value "4K42")
      (footprint "0603-RW")
      (description "CHIP 4.42K OHM 100PPM +-1% 0603 WALS L")
      (fields
        (field (name "MFG") "WALSIN (華新)")
        (field (name "Comment") "T502442102399")
        (field (name "CREAT_NAME") "Nathan")
      )
      (libsource (lib "Q-Resistors") (part "RES0603 1/10W 1% 4.42K OHM_WALSIN"))
    )
    (comp (ref "R300")
      (value "49R9")
      (footprint "0402-RW")
      (description "CHIP RES 49.9 OMH 1/16W 1% 0402")
      (fields (field (name "Comment") "QCF161241-4999") (field (name "CREATE_NAME") "GordonL@Deftronics"))
      (libsource (lib "Q-Resistors") (part "RES0402 1/16W 1% 49.9R OHM"))
    )
    (comp (ref "R327")
      (value "5K9")
      (footprint "0603-RW")
      (description "CHIP 5.9K OHM  100PPM +-1% 0603 WALS L")
      (fields
        (field (name "POWER") "~{1}10W")
        (field (name "MFG") "WALSIN (華新)")
        (field (name "CREAT_NAME") "Nathan")
      )
      (libsource (lib "Q-Resistors") (part "RES0603 1/10W 1% 5.9K OHM_WALSIN"))
    )
    (comp (ref "R329")
      (value "4K42")
      (footprint "0603-RW")
      (description "CHIP 4.42K OHM 100PPM +-1% 0603 WALS L")
      (fields
        (field (name "MFG") "WALSIN (華新)")
        (field (name "Comment") "T502442102399")
        (field (name "CREAT_NAME") "Nathan")
      )
      (libsource (lib "Q-Resistors") (part "RES0603 1/10W 1% 4.42K OHM_WALSIN"))
    )
    (comp (ref "R330")
      (value "5K9")
      (footprint "0603-RW")
      (description "CHIP 5.9K OHM  100PPM +-1% 0603 WALS L")
      (fields
        (field (name "POWER") "~{1}10W")
        (field (name "MFG") "WALSIN (華新)")
        (field (name "CREAT_NAME") "Nathan")
      )
      (libsource (lib "Q-Resistors") (part "RES0603 1/10W 1% 5.9K OHM_WALSIN"))
    )
    (comp (ref "R331")
      (value "1M")
      (footprint "0603-RW")
      (description "GP CHIP RES. 1M OHM 1/10W 1% 0603")
      (fields (field (name "Comment") "QCF011030-1004"))
      (libsource (lib "Q-Resistors") (part "RES0603 1/10W 1% 1M OHM"))
    )
    (comp (ref "R332")
      (value "100R")
      (footprint "0603-RW")
      (description "GP CHIP RES. 100 OHM 1/10W 1% 0603")
      (fields (field (name "Comment") "QCF011030-1000"))
      (libsource (lib "Q-Resistors") (part "RES0603 1/10W 1% 100 OHM"))
    )
    (comp (ref "R333")
      (value "6.8K")
      (footprint "0603-RW")
      (description "GP CHIP RES. 6.8K OHM 1/10W 1% 0603")
      (fields (field (name "Comment") "QCF011030-6801"))
      (libsource (lib "Q-Resistors") (part "RES0603 1/10W 1% 6.8K OHM"))
    )
    (comp (ref "R334")
      (value "1M")
      (footprint "0603-RW")
      (description "GP CHIP RES. 1M OHM 1/10W 1% 0603")
      (fields (field (name "Comment") "QCF011030-1004"))
      (libsource (lib "Q-Resistors") (part "RES0603 1/10W 1% 1M OHM"))
    )
    (comp (ref "R336")
      (value "5K9")
      (footprint "0603-RW")
      (description "CHIP 5.9K OHM  100PPM +-1% 0603 WALS L")
      (fields
        (field (name "POWER") "~{1}10W")
        (field (name "MFG") "WALSIN (華新)")
        (field (name "CREAT_NAME") "Nathan")
      )
      (libsource (lib "Q-Resistors") (part "RES0603 1/10W 1% 5.9K OHM_WALSIN"))
    )
    (comp (ref "R400")
      (value "49R9")
      (footprint "0402-RW")
      (description "CHIP RES 49.9 OMH 1/16W 1% 0402")
      (fields (field (name "Comment") "QCF161241-4999") (field (name "CREATE_NAME") "GordonL@Deftronics"))
      (libsource (lib "Q-Resistors") (part "RES0402 1/16W 1% 49.9R OHM"))
    )
    (comp (ref "R681")
      (value "22R")
      (footprint "0402-RW")
      (description "CHIP RES 22 OHM 1/16W 1% 0402")
      (fields (field (name "MFG") "WALSIN") (field (name "Comment") "QCF161242-2209"))
      (libsource (lib "Q-Resistors") (part "RES0402 1/16W 1% 22 OHM"))
    )
    (comp (ref "R682")
      (value "22R")
      (footprint "0402-RW")
      (description "CHIP RES 22 OHM 1/16W 1% 0402")
      (fields (field (name "MFG") "WALSIN") (field (name "Comment") "QCF161242-2209"))
      (libsource (lib "Q-Resistors") (part "RES0402 1/16W 1% 22 OHM"))
    )
    (comp (ref "R683")
      (value "22R")
      (footprint "0402-RW")
      (description "CHIP RES 22 OHM 1/16W 1% 0402")
      (fields (field (name "MFG") "WALSIN") (field (name "Comment") "QCF161242-2209"))
      (libsource (lib "Q-Resistors") (part "RES0402 1/16W 1% 22 OHM"))
    )
    (comp (ref "R684")
      (value "22R")
      (footprint "0402-RW")
      (description "CHIP RES 22 OHM 1/16W 1% 0402")
      (fields (field (name "MFG") "WALSIN") (field (name "Comment") "QCF161242-2209"))
      (libsource (lib "Q-Resistors") (part "RES0402 1/16W 1% 22 OHM"))
    )
    (comp (ref "TP8") (value "TP") (footprint "TP_1.0mm") (libsource (lib "Temporary") (part "TP")))
    (comp (ref "TP9") (value "TP") (footprint "TP_1.0mm") (libsource (lib "Temporary") (part "TP")))
    (comp (ref "TP24") (value "TP") (footprint "TP_1.0mm") (libsource (lib "Temporary") (part "TP")))
    (comp (ref "TP25") (value "TP") (footprint "TP_1.0mm") (libsource (lib "Temporary") (part "TP")))
    (comp (ref "TP31") (value "TP") (footprint "TP_1.0mm") (libsource (lib "Temporary") (part "TP")))
    (comp (ref "TP32") (value "TP") (footprint "TP_1.0mm") (libsource (lib "Temporary") (part "TP")))
    (comp (ref "TP33") (value "TP") (footprint "TP_1.0mm") (libsource (lib "") (part "TP_1")))
    (comp (ref "TP35") (value "TP") (footprint "TP_1.0mm") (libsource (lib "Temporary") (part "TP")))
    (comp (ref "TP36") (value "TP") (footprint "TP_1.0mm") (libsource (lib "Temporary") (part "TP")))
    (comp (ref "TP37") (value "TP") (footprint "TP_1.0mm") (libsource (lib "Temporary") (part "TP")))
    (comp (ref "TP38") (value "TP") (footprint "TP_1.0mm") (libsource (lib "") (part "TP_1")))
    (comp (ref "TP40") (value "TP") (footprint "TP_1.0mm") (libsource (lib "Temporary") (part "TP")))
    (comp (ref "TP44") (value "TP") (footprint "TP_1.0mm") (libsource (lib "Temporary") (part "TP")))
    (comp (ref "TP45") (value "TP") (footprint "TP_1.0mm") (libsource (lib "Temporary") (part "TP")))
    (comp (ref "TP46") (value "TP") (footprint "TP_1.0mm") (libsource (lib "") (part "TP_1")))
    (comp (ref "TP49") (value "TP") (footprint "TP_1.0mm") (libsource (lib "Temporary") (part "TP")))
    (comp (ref "TP50") (value "TP") (footprint "TP_1.0mm") (libsource (lib "Temporary") (part "TP")))
    (comp (ref "TP51") (value "TP") (footprint "TP_1.0mm") (libsource (lib "") (part "TP_1")))
    (comp (ref "TP92")
      (value "D1.2V")
      (footprint "TP_1.2mm")
      (description "TP")
      (libsource (lib "Temporary") (part "TP"))
    )
    (comp (ref "TP93")
      (value "D1.2V")
      (footprint "TP_1.2mm")
      (description "TP")
      (libsource (lib "Temporary") (part "TP"))
    )
    (comp (ref "TP94")
      (value "D1.2V")
      (footprint "TP_1.2mm")
      (description "TP")
      (libsource (lib "Temporary") (part "TP"))
    )
    (comp (ref "TP95")
      (value "D1.2V")
      (footprint "TP_1.2mm")
      (description "TP")
      (libsource (lib "Temporary") (part "TP"))
    )
    (comp (ref "TP96")
      (value "D1.2V")
      (footprint "TP_1.2mm")
      (description "TP")
      (libsource (lib "Temporary") (part "TP"))
    )
    (comp (ref "TP97")
      (value "D1.2V")
      (footprint "TP_1.2mm")
      (description "TP")
      (libsource (lib "Temporary") (part "TP"))
    )
    (comp (ref "TP98")
      (value "D1.2V")
      (footprint "TP_1.2mm")
      (description "TP")
      (libsource (lib "Temporary") (part "TP"))
    )
    (comp (ref "TP99")
      (value "D1.2V")
      (footprint "TP_1.2mm")
      (description "TP")
      (libsource (lib "Temporary") (part "TP"))
    )
    (comp (ref "TP100")
      (value "D1.2V")
      (footprint "TP_1.2mm")
      (description "TP")
      (libsource (lib "Temporary") (part "TP"))
    )
    (comp (ref "TP101")
      (value "D1.2V")
      (footprint "TP_1.2mm")
      (description "TP")
      (libsource (lib "Temporary") (part "TP"))
    )
    (comp (ref "U1")
      (value "RCI000740-1001")
      (footprint "SO14")
      (description "GP IC 14P TL074CDT PLASTIC MICRO PACKAG")
      (fields (field (name "MFG") "ST") (field (name "MFG PART") "TL074C"))
      (libsource (lib "R-Semiconductors") (part "TL074C"))
    )
    (comp (ref "U2")
      (value "RCI002068-0001")
      (footprint "DMP8")
      (description "IC OP AMP NJM2068 DUAL SO-8")
      (fields
        (field (name "MFG") "JRC")
        (field (name "MFG PART") "NJM2068")
        (field (name "CREATE_NAME") "GordonL@Deftronics")
      )
      (libsource (lib "R-Semiconductors") (part "NJM2068"))
    )
    (comp (ref "U4")
      (value "RCI000740-1001")
      (footprint "SO14")
      (description "GP IC 14P TL074CDT PLASTIC MICRO PACKAG")
      (fields (field (name "MFG") "ST") (field (name "MFG PART") "TL074C"))
      (libsource (lib "R-Semiconductors") (part "TL074C"))
    )
    (comp (ref "U5")
      (value "RCI002068-0001")
      (footprint "DMP8")
      (description "IC OP AMP NJM2068 DUAL SO-8")
      (fields
        (field (name "MFG") "JRC")
        (field (name "MFG PART") "NJM2068")
        (field (name "CREATE_NAME") "GordonL@Deftronics")
      )
      (libsource (lib "R-Semiconductors") (part "NJM2068"))
    )
    (comp (ref "U48")
      (value "RCI004580-0001")
      (footprint "DMP8")
      (description "IC OP AMP NJM4580  DUAL SO-8")
      (fields
        (field (name "MFG") "JRC")
        (field (name "MFG PART") "NJM4580")
        (field (name "CREATE_NAME") "GordonL@Deftronics")
      )
      (libsource (lib "R-Semiconductors") (part "NJM4580"))
    )
    (comp (ref "U49")
      (value "RCI004580-0001")
      (footprint "DMP8")
      (description "IC OP AMP NJM4580  DUAL SO-8")
      (fields
        (field (name "MFG") "JRC")
        (field (name "MFG PART") "NJM4580")
        (field (name "CREATE_NAME") "GordonL@Deftronics")
      )
      (libsource (lib "R-Semiconductors") (part "NJM4580"))
    )
  )
  (nets
    (net (code "1") (name "+15V") (class "Default")
      (node (ref "C247") (pin "1") (pinfunction "1_1") (pintype "passive"))
      (node (ref "C67") (pin "1") (pinfunction "1_1") (pintype "passive"))
      (node (ref "C68") (pin "1") (pinfunction "1_1") (pintype "passive"))
      (node (ref "C69") (pin "1") (pinfunction "1_1") (pintype "passive"))
      (node (ref "C72") (pin "1") (pinfunction "1_1") (pintype "passive"))
      (node (ref "C73") (pin "1") (pinfunction "1_1") (pintype "passive"))
      (node (ref "C74") (pin "1") (pinfunction "1_1") (pintype "passive"))
      (node (ref "C75") (pin "1") (pinfunction "1_1") (pintype "passive"))
      (node (ref "C76") (pin "1") (pinfunction "1_1") (pintype "passive"))
      (node (ref "C77") (pin "1") (pinfunction "1_1") (pintype "passive"))
      (node (ref "C78") (pin "1") (pinfunction "1_1") (pintype "passive"))
      (node (ref "C79") (pin "1") (pinfunction "1_1") (pintype "passive"))
      (node (ref "C81") (pin "1") (pinfunction "1_1") (pintype "passive"))
      (node (ref "D12") (pin "2") (pinfunction "K_2") (pintype "passive"))
      (node (ref "D13") (pin "2") (pinfunction "K_2") (pintype "passive"))
      (node (ref "D14") (pin "2") (pinfunction "K_2") (pintype "passive"))
      (node (ref "D15") (pin "2") (pinfunction "K_2") (pintype "passive"))
      (node (ref "D4") (pin "2") (pinfunction "K_2") (pintype "passive"))
      (node (ref "D5") (pin "2") (pinfunction "K_2") (pintype "passive"))
      (node (ref "D6") (pin "2") (pinfunction "K_2") (pintype "passive"))
      (node (ref "D7") (pin "2") (pinfunction "K_2") (pintype "passive"))
      (node (ref "U1") (pin "4") (pinfunction "+V_4") (pintype "power_in"))
      (node (ref "U2") (pin "8") (pinfunction "8_8") (pintype "passive"))
      (node (ref "U4") (pin "4") (pinfunction "+V_4") (pintype "power_in"))
      (node (ref "U48") (pin "8") (pinfunction "8_8") (pintype "passive"))
      (node (ref "U49") (pin "8") (pinfunction "8_8") (pintype "passive"))
      (node (ref "U5") (pin "8") (pinfunction "8_8") (pintype "passive"))
    )
    (net (code "2") (name "-15V") (class "Default")
      (node (ref "C100") (pin "2") (pinfunction "2_2") (pintype "passive"))
      (node (ref "C101") (pin "2") (pinfunction "2_2") (pintype "passive"))
      (node (ref "C103") (pin "2") (pinfunction "2_2") (pintype "passive"))
      (node (ref "C104") (pin "2") (pinfunction "2_2") (pintype "passive"))
      (node (ref "C107") (pin "2") (pinfunction "2_2") (pintype "passive"))
      (node (ref "C88") (pin "2") (pinfunction "2_2") (pintype "passive"))
      (node (ref "C89") (pin "2") (pinfunction "2_2") (pintype "passive"))
      (node (ref "C90") (pin "2") (pinfunction "2_2") (pintype "passive"))
      (node (ref "C93") (pin "2") (pinfunction "2_2") (pintype "passive"))
      (node (ref "C94") (pin "2") (pinfunction "2_2") (pintype "passive"))
      (node (ref "C95") (pin "2") (pinfunction "2_2") (pintype "passive"))
      (node (ref "C96") (pin "2") (pinfunction "2_2") (pintype "passive"))
      (node (ref "C97") (pin "2") (pinfunction "2_2") (pintype "passive"))
      (node (ref "D12") (pin "1") (pinfunction "A_1") (pintype "passive"))
      (node (ref "D13") (pin "1") (pinfunction "A_1") (pintype "passive"))
      (node (ref "D14") (pin "1") (pinfunction "A_1") (pintype "passive"))
      (node (ref "D15") (pin "1") (pinfunction "A_1") (pintype "passive"))
      (node (ref "D32") (pin "2") (pinfunction "K_2") (pintype "passive"))
      (node (ref "D34") (pin "2") (pinfunction "K_2") (pintype "passive"))
      (node (ref "D4") (pin "1") (pinfunction "A_1") (pintype "passive"))
      (node (ref "D5") (pin "1") (pinfunction "A_1") (pintype "passive"))
      (node (ref "D6") (pin "1") (pinfunction "A_1") (pintype "passive"))
      (node (ref "D7") (pin "1") (pinfunction "A_1") (pintype "passive"))
      (node (ref "U1") (pin "11") (pinfunction "-V_11") (pintype "power_in"))
      (node (ref "U2") (pin "4") (pinfunction "4_4") (pintype "passive"))
      (node (ref "U4") (pin "11") (pinfunction "-V_11") (pintype "power_in"))
      (node (ref "U48") (pin "4") (pinfunction "4_4") (pintype "passive"))
      (node (ref "U49") (pin "4") (pinfunction "4_4") (pintype "passive"))
      (node (ref "U5") (pin "4") (pinfunction "4_4") (pintype "passive"))
    )
    (net (code "3") (name "/1C_N") (class "Default")
      (node (ref "C25") (pin "1") (pinfunction "1_1") (pintype "passive"))
      (node (ref "Q7") (pin "6") (pinfunction "C_6") (pintype "passive"))
      (node (ref "Q8") (pin "6") (pinfunction "C_6") (pintype "passive"))
      (node (ref "Q9") (pin "6") (pinfunction "C_6") (pintype "passive"))
      (node (ref "R203") (pin "1") (pinfunction "1_1") (pintype "passive"))
      (node (ref "R24") (pin "2") (pinfunction "2_2") (pintype "passive"))
      (node (ref "R50") (pin "1") (pinfunction "1_1") (pintype "passive"))
    )
    (net (code "4") (name "/1C_P") (class "Default")
      (node (ref "C25") (pin "2") (pinfunction "2_2") (pintype "passive"))
      (node (ref "Q7") (pin "3") (pinfunction "C_3") (pintype "passive"))
      (node (ref "Q8") (pin "3") (pinfunction "C_3") (pintype "passive"))
      (node (ref "Q9") (pin "3") (pinfunction "C_3") (pintype "passive"))
      (node (ref "R18") (pin "1") (pinfunction "1_1") (pintype "passive"))
      (node (ref "R191") (pin "1") (pinfunction "1_1") (pintype "passive"))
      (node (ref "R9") (pin "2") (pinfunction "2_2") (pintype "passive"))
    )
    (net (code "5") (name "/2C_N") (class "Default")
      (node (ref "C261") (pin "1") (pinfunction "1_1") (pintype "passive"))
      (node (ref "Q11") (pin "6") (pinfunction "C_6") (pintype "passive"))
      (node (ref "Q12") (pin "6") (pinfunction "C_6") (pintype "passive"))
      (node (ref "Q13") (pin "6") (pinfunction "C_6") (pintype "passive"))
      (node (ref "R186") (pin "1") (pinfunction "1_1") (pintype "passive"))
      (node (ref "R223") (pin "1") (pinfunction "1_1") (pintype "passive"))
      (node (ref "R52") (pin "2") (pinfunction "2_2") (pintype "passive"))
    )
    (net (code "6") (name "/2C_P") (class "Default")
      (node (ref "C261") (pin "2") (pinfunction "2_2") (pintype "passive"))
      (node (ref "Q11") (pin "3") (pinfunction "C_3") (pintype "passive"))
      (node (ref "Q12") (pin "3") (pinfunction "C_3") (pintype "passive"))
      (node (ref "Q13") (pin "3") (pinfunction "C_3") (pintype "passive"))
      (node (ref "R153") (pin "1") (pinfunction "1_1") (pintype "passive"))
      (node (ref "R216") (pin "1") (pinfunction "1_1") (pintype "passive"))
      (node (ref "R51") (pin "2") (pinfunction "2_2") (pintype "passive"))
    )
    (net (code "7") (name "/BIAS3") (class "Default")
      (node (ref "R142") (pin "2") (pinfunction "2_2") (pintype "passive"))
      (node (ref "R200") (pin "2") (pinfunction "2_2") (pintype "passive"))
      (node (ref "R211") (pin "2") (pinfunction "2_2") (pintype "passive"))
      (node (ref "R221") (pin "2") (pinfunction "2_2") (pintype "passive"))
    )
    (net (code "8") (name "/IN1_N") (class "Default")
      (node (ref "C32") (pin "2") (pinfunction "2_2") (pintype "passive"))
      (node (ref "D7") (pin "3") (pinfunction "C_3") (pintype "passive"))
      (node (ref "Q7") (pin "2") (pinfunction "C_2") (pintype "passive"))
      (node (ref "Q8") (pin "2") (pinfunction "C_2") (pintype "passive"))
      (node (ref "Q9") (pin "2") (pinfunction "C_2") (pintype "passive"))
      (node (ref "R203") (pin "2") (pinfunction "2_2") (pintype "passive"))
      (node (ref "R4") (pin "1") (pinfunction "1_1") (pintype "passive"))
      (node (ref "R48") (pin "1") (pinfunction "1_1") (pintype "passive"))
      (node (ref "R53") (pin "2") (pinfunction "2_2") (pintype "passive"))
      (node (ref "TP38") (pin "1") (pinfunction "1_1") (pintype "passive"))
    )
    (net (code "9") (name "/IN1_P") (class "Default")
      (node (ref "C17") (pin "2") (pinfunction "2_2") (pintype "passive"))
      (node (ref "D6") (pin "3") (pinfunction "C_3") (pintype "passive"))
      (node (ref "Q7") (pin "5") (pinfunction "B_5") (pintype "passive"))
      (node (ref "Q8") (pin "5") (pinfunction "B_5") (pintype "passive"))
      (node (ref "Q9") (pin "5") (pinfunction "B_5") (pintype "passive"))
      (node (ref "R191") (pin "2") (pinfunction "2_2") (pintype "passive"))
      (node (ref "R22") (pin "2") (pinfunction "2_2") (pintype "passive"))
      (node (ref "R31") (pin "2") (pinfunction "2_2") (pintype "passive"))
      (node (ref "R4") (pin "2") (pinfunction "2_2") (pintype "passive"))
      (node (ref "TP33") (pin "1") (pinfunction "1_1") (pintype "passive"))
    )
    (net (code "10") (name "/IN2_N") (class "Default")
      (node (ref "C267") (pin "2") (pinfunction "2_2") (pintype "passive"))
      (node (ref "D15") (pin "3") (pinfunction "C_3") (pintype "passive"))
      (node (ref "Q11") (pin "2") (pinfunction "C_2") (pintype "passive"))
      (node (ref "Q12") (pin "2") (pinfunction "C_2") (pintype "passive"))
      (node (ref "Q13") (pin "2") (pinfunction "C_2") (pintype "passive"))
      (node (ref "R182") (pin "1") (pinfunction "1_1") (pintype "passive"))
      (node (ref "R188") (pin "2") (pinfunction "2_2") (pintype "passive"))
      (node (ref "R21") (pin "1") (pinfunction "1_1") (pintype "passive"))
      (node (ref "R223") (pin "2") (pinfunction "2_2") (pintype "passive"))
      (node (ref "TP51") (pin "1") (pinfunction "1_1") (pintype "passive"))
    )
    (net (code "11") (name "/IN2_P") (class "Default")
      (node (ref "C144") (pin "2") (pinfunction "2_2") (pintype "passive"))
      (node (ref "D14") (pin "3") (pinfunction "C_3") (pintype "passive"))
      (node (ref "Q11") (pin "5") (pinfunction "B_5") (pintype "passive"))
      (node (ref "Q12") (pin "5") (pinfunction "B_5") (pintype "passive"))
      (node (ref "Q13") (pin "5") (pinfunction "B_5") (pintype "passive"))
      (node (ref "R156") (pin "2") (pinfunction "2_2") (pintype "passive"))
      (node (ref "R162") (pin "2") (pinfunction "2_2") (pintype "passive"))
      (node (ref "R21") (pin "2") (pinfunction "2_2") (pintype "passive"))
      (node (ref "R216") (pin "2") (pinfunction "2_2") (pintype "passive"))
      (node (ref "TP46") (pin "1") (pinfunction "1_1") (pintype "passive"))
    )
    (net (code "12") (name "/LINE1_N") (class "Default")
      (node (ref "C19") (pin "2") (pinfunction "2_2") (pintype "passive"))
      (node (ref "C781") (pin "2") (pinfunction "2_2") (pintype "passive"))
      (node (ref "J4") (pin "R") (pinfunction "R_R") (pintype "passive"))
      (node (ref "R19") (pin "1") (pinfunction "1_1") (pintype "passive"))
      (node (ref "TP92") (pin "1") (pinfunction "1_1") (pintype "passive"))
    )
    (net (code "13") (name "/LINE1_P") (class "Default")
      (node (ref "C241") (pin "1") (pinfunction "1_1") (pintype "passive"))
      (node (ref "C780") (pin "1") (pinfunction "1_1") (pintype "passive"))
      (node (ref "J4") (pin "T") (pinfunction "T_T") (pintype "passive"))
      (node (ref "R1") (pin "1") (pinfunction "1_1") (pintype "passive"))
      (node (ref "TP93") (pin "1") (pinfunction "1_1") (pintype "passive"))
    )
    (net (code "14") (name "/LINE2_N") (class "Default")
      (node (ref "C148") (pin "2") (pinfunction "2_2") (pintype "passive"))
      (node (ref "C783") (pin "2") (pinfunction "2_2") (pintype "passive"))
      (node (ref "J5") (pin "R") (pinfunction "R_R") (pintype "passive"))
      (node (ref "R154") (pin "1") (pinfunction "1_1") (pintype "passive"))
      (node (ref "TP99") (pin "1") (pinfunction "1_1") (pintype "passive"))
    )
    (net (code "15") (name "/LINE2_P") (class "Default")
      (node (ref "C138") (pin "1") (pinfunction "1_1") (pintype "passive"))
      (node (ref "C782") (pin "1") (pinfunction "1_1") (pintype "passive"))
      (node (ref "J5") (pin "T") (pinfunction "T_T") (pintype "passive"))
      (node (ref "R332") (pin "1") (pinfunction "1_1") (pintype "passive"))
      (node (ref "TP98") (pin "1") (pinfunction "1_1") (pintype "passive"))
    )
    (net (code "16") (name "/MIC1_N") (class "Default")
      (node (ref "C785") (pin "2") (pinfunction "2_2") (pintype "passive"))
      (node (ref "J4") (pin "3") (pinfunction "3_3") (pintype "passive"))
      (node (ref "R682") (pin "2") (pinfunction "2_2") (pintype "passive"))
      (node (ref "TP96") (pin "1") (pinfunction "1_1") (pintype "passive"))
    )
    (net (code "17") (name "/MIC1_P") (class "Default")
      (node (ref "C784") (pin "1") (pinfunction "1_1") (pintype "passive"))
      (node (ref "J4") (pin "2") (pinfunction "2_2") (pintype "passive"))
      (node (ref "R681") (pin "2") (pinfunction "2_2") (pintype "passive"))
      (node (ref "TP95") (pin "1") (pinfunction "1_1") (pintype "passive"))
    )
    (net (code "18") (name "/MIC2_N") (class "Default")
      (node (ref "C787") (pin "2") (pinfunction "2_2") (pintype "passive"))
      (node (ref "J5") (pin "3") (pinfunction "3_3") (pintype "passive"))
      (node (ref "R684") (pin "2") (pinfunction "2_2") (pintype "passive"))
      (node (ref "TP100") (pin "1") (pinfunction "1_1") (pintype "passive"))
    )
    (net (code "19") (name "/MIC2_P") (class "Default")
      (node (ref "C786") (pin "1") (pinfunction "1_1") (pintype "passive"))
      (node (ref "J5") (pin "2") (pinfunction "2_2") (pintype "passive"))
      (node (ref "R683") (pin "2") (pinfunction "2_2") (pintype "passive"))
      (node (ref "TP101") (pin "1") (pinfunction "1_1") (pintype "passive"))
    )
    (net (code "20") (name "/MIC12_N") (class "Default")
      (node (ref "C140") (pin "1") (pinfunction "1_1") (pintype "passive"))
      (node (ref "C31") (pin "2") (pinfunction "2_2") (pintype "passive"))
      (node (ref "R17") (pin "1") (pinfunction "1_1") (pintype "passive"))
      (node (ref "R236") (pin "2") (pinfunction "2_2") (pintype "passive"))
      (node (ref "R37") (pin "1") (pinfunction "1_1") (pintype "passive"))
      (node (ref "R682") (pin "1") (pinfunction "1_1") (pintype "passive"))
    )
    (net (code "21") (name "/MIC12_P") (class "Default")
      (node (ref "C22") (pin "1") (pinfunction "1_1") (pintype "passive"))
      (node (ref "C242") (pin "1") (pinfunction "1_1") (pintype "passive"))
      (node (ref "R2") (pin "2") (pinfunction "2_2") (pintype "passive"))
      (node (ref "R220") (pin "2") (pinfunction "2_2") (pintype "passive"))
      (node (ref "R37") (pin "2") (pinfunction "2_2") (pintype "passive"))
      (node (ref "R681") (pin "1") (pinfunction "1_1") (pintype "passive"))
    )
    (net (code "22") (name "/MIC22_N") (class "Default")
      (node (ref "C266") (pin "2") (pinfunction "2_2") (pintype "passive"))
      (node (ref "C269") (pin "1") (pinfunction "1_1") (pintype "passive"))
      (node (ref "R152") (pin "1") (pinfunction "1_1") (pintype "passive"))
      (node (ref "R172") (pin "1") (pinfunction "1_1") (pintype "passive"))
      (node (ref "R264") (pin "2") (pinfunction "2_2") (pintype "passive"))
      (node (ref "R684") (pin "1") (pinfunction "1_1") (pintype "passive"))
    )
    (net (code "23") (name "/MIC22_P") (class "Default")
      (node (ref "C159") (pin "1") (pinfunction "1_1") (pintype "passive"))
      (node (ref "C262") (pin "1") (pinfunction "1_1") (pintype "passive"))
      (node (ref "R172") (pin "2") (pinfunction "2_2") (pintype "passive"))
      (node (ref "R253") (pin "2") (pinfunction "2_2") (pintype "passive"))
      (node (ref "R333") (pin "2") (pinfunction "2_2") (pintype "passive"))
      (node (ref "R683") (pin "1") (pinfunction "1_1") (pintype "passive"))
    )
    (net (code "24") (name "/POT12") (class "Default")
      (node (ref "B14") (pin "2") (pinfunction "2_2") (pintype "passive"))
      (node (ref "JA11A") (pin "2") (pinfunction "2_2") (pintype "passive"))
    )
    (net (code "25") (name "/POT12F") (class "Default")
      (node (ref "B14") (pin "1") (pinfunction "1_1") (pintype "passive"))
      (node (ref "C133") (pin "2") (pinfunction "2_2") (pintype "passive"))
      (node (ref "C702") (pin "1") (pinfunction "1_1") (pintype "passive"))
      (node (ref "R8") (pin "2") (pinfunction "2_2") (pintype "passive"))
    )
    (net (code "26") (name "/POT13") (class "Default")
      (node (ref "B15") (pin "2") (pinfunction "2_2") (pintype "passive"))
      (node (ref "JA11A") (pin "1") (pinfunction "1_1") (pintype "passive"))
    )
    (net (code "27") (name "/POT13F") (class "Default")
      (node (ref "B15") (pin "1") (pinfunction "1_1") (pintype "passive"))
      (node (ref "C703") (pin "1") (pinfunction "1_1") (pintype "passive"))
      (node (ref "R300") (pin "2") (pinfunction "2_2") (pintype "passive"))
      (node (ref "R8") (pin "1") (pinfunction "1_1") (pintype "passive"))
      (node (ref "TP8") (pin "1") (pinfunction "1_1") (pintype "passive"))
    )
    (net (code "28") (name "/POT14") (class "Default")
      (node (ref "C701") (pin "1") (pinfunction "1_1") (pintype "passive"))
      (node (ref "JA11A") (pin "3") (pinfunction "3_3") (pintype "passive"))
      (node (ref "R237") (pin "2") (pinfunction "2_2") (pintype "passive"))
      (node (ref "R33") (pin "1") (pinfunction "1_1") (pintype "passive"))
      (node (ref "R42") (pin "1") (pinfunction "1_1") (pintype "passive"))
      (node (ref "TP24") (pin "1") (pinfunction "1_1") (pintype "passive"))
    )
    (net (code "29") (name "/POT15") (class "Default")
      (node (ref "C700") (pin "1") (pinfunction "1_1") (pintype "passive"))
      (node (ref "JA11A") (pin "4") (pinfunction "4_4") (pintype "passive"))
      (node (ref "R249") (pin "2") (pinfunction "2_2") (pintype "passive"))
      (node (ref "R32") (pin "1") (pinfunction "1_1") (pintype "passive"))
      (node (ref "R329") (pin "1") (pinfunction "1_1") (pintype "passive"))
      (node (ref "TP25") (pin "1") (pinfunction "1_1") (pintype "passive"))
    )
    (net (code "30") (name "/POT22") (class "Default")
      (node (ref "B16") (pin "2") (pinfunction "2_2") (pintype "passive"))
      (node (ref "JA11A") (pin "9") (pinfunction "9_9") (pintype "passive"))
    )
    (net (code "31") (name "/POT22F") (class "Default")
      (node (ref "B16") (pin "1") (pinfunction "1_1") (pintype "passive"))
      (node (ref "C141") (pin "2") (pinfunction "2_2") (pintype "passive"))
      (node (ref "C705") (pin "1") (pinfunction "1_1") (pintype "passive"))
      (node (ref "R36") (pin "2") (pinfunction "2_2") (pintype "passive"))
    )
    (net (code "32") (name "/POT23") (class "Default")
      (node (ref "B17") (pin "2") (pinfunction "2_2") (pintype "passive"))
      (node (ref "JA11A") (pin "10") (pinfunction "10_10") (pintype "passive"))
    )
    (net (code "33") (name "/POT23F") (class "Default")
      (node (ref "B17") (pin "1") (pinfunction "1_1") (pintype "passive"))
      (node (ref "C704") (pin "1") (pinfunction "1_1") (pintype "passive"))
      (node (ref "R166") (pin "2") (pinfunction "2_2") (pintype "passive"))
      (node (ref "R36") (pin "1") (pinfunction "1_1") (pintype "passive"))
      (node (ref "TP9") (pin "1") (pinfunction "1_1") (pintype "passive"))
    )
    (net (code "34") (name "/POT24") (class "Default")
      (node (ref "C707") (pin "1") (pinfunction "1_1") (pintype "passive"))
      (node (ref "JA11A") (pin "7") (pinfunction "7_7") (pintype "passive"))
      (node (ref "R265") (pin "2") (pinfunction "2_2") (pintype "passive"))
      (node (ref "R290") (pin "1") (pinfunction "1_1") (pintype "passive"))
      (node (ref "R34") (pin "1") (pinfunction "1_1") (pintype "passive"))
      (node (ref "TP35") (pin "1") (pinfunction "1_1") (pintype "passive"))
    )
    (net (code "35") (name "/POT25") (class "Default")
      (node (ref "C706") (pin "1") (pinfunction "1_1") (pintype "passive"))
      (node (ref "JA11A") (pin "8") (pinfunction "8_8") (pintype "passive"))
      (node (ref "R271") (pin "2") (pinfunction "2_2") (pintype "passive"))
      (node (ref "R286") (pin "1") (pinfunction "1_1") (pintype "passive"))
      (node (ref "R294") (pin "1") (pinfunction "1_1") (pintype "passive"))
      (node (ref "TP40") (pin "1") (pinfunction "1_1") (pintype "passive"))
    )
    (net (code "36") (name "5V") (class "Default")
      (node (ref "D1") (pin "1") (pinfunction "A_1") (pintype "passive"))
      (node (ref "Q19") (pin "6") (pinfunction "D_6") (pintype "passive"))
      (node (ref "Q20") (pin "6") (pinfunction "D_6") (pintype "passive"))
      (node (ref "Q21") (pin "6") (pinfunction "D_6") (pintype "passive"))
      (node (ref "Q22") (pin "6") (pinfunction "D_6") (pintype "passive"))
      (node (ref "Q23") (pin "6") (pinfunction "D_6") (pintype "passive"))
      (node (ref "Q24") (pin "6") (pinfunction "D_6") (pintype "passive"))
      (node (ref "Q25") (pin "6") (pinfunction "D_6") (pintype "passive"))
      (node (ref "Q26") (pin "6") (pinfunction "D_6") (pintype "passive"))
    )
    (net (code "37") (name "ADC_AUXL+") (class "Default")
      (node (ref "Q21") (pin "1") (pinfunction "S_1") (pintype "passive"))
      (node (ref "Q21") (pin "4") (pinfunction "S_4") (pintype "passive"))
    )
    (net (code "38") (name "ADC_AUXL-") (class "Default")
      (node (ref "Q25") (pin "1") (pinfunction "S_1") (pintype "passive"))
      (node (ref "Q25") (pin "4") (pinfunction "S_4") (pintype "passive"))
    )
    (net (code "39") (name "ADC_AUXR+") (class "Default")
      (node (ref "Q26") (pin "1") (pinfunction "S_1") (pintype "passive"))
      (node (ref "Q26") (pin "4") (pinfunction "S_4") (pintype "passive"))
    )
    (net (code "40") (name "ADC_AUXR-") (class "Default")
      (node (ref "Q22") (pin "1") (pinfunction "S_1") (pintype "passive"))
      (node (ref "Q22") (pin "4") (pinfunction "S_4") (pintype "passive"))
    )
    (net (code "41") (name "ADC_IN1+") (class "Default")
      (node (ref "C106") (pin "1") (pinfunction "1_1") (pintype "passive"))
      (node (ref "Q23") (pin "1") (pinfunction "S_1") (pintype "passive"))
      (node (ref "Q23") (pin "4") (pinfunction "S_4") (pintype "passive"))
      (node (ref "R146") (pin "2") (pinfunction "2_2") (pintype "passive"))
      (node (ref "R239") (pin "2") (pinfunction "2_2") (pintype "passive"))
    )
    (net (code "42") (name "ADC_IN1-") (class "Default")
      (node (ref "C106") (pin "2") (pinfunction "2_2") (pintype "passive"))
      (node (ref "Q19") (pin "1") (pinfunction "S_1") (pintype "passive"))
      (node (ref "Q19") (pin "4") (pinfunction "S_4") (pintype "passive"))
      (node (ref "R252") (pin "2") (pinfunction "2_2") (pintype "passive"))
      (node (ref "R331") (pin "2") (pinfunction "2_2") (pintype "passive"))
    )
    (net (code "43") (name "ADC_IN2+") (class "Default")
      (node (ref "C259") (pin "1") (pinfunction "1_1") (pintype "passive"))
      (node (ref "Q20") (pin "1") (pinfunction "S_1") (pintype "passive"))
      (node (ref "Q20") (pin "4") (pinfunction "S_4") (pintype "passive"))
      (node (ref "R269") (pin "2") (pinfunction "2_2") (pintype "passive"))
      (node (ref "R334") (pin "2") (pinfunction "2_2") (pintype "passive"))
    )
    (net (code "44") (name "ADC_IN2-") (class "Default")
      (node (ref "C259") (pin "2") (pinfunction "2_2") (pintype "passive"))
      (node (ref "Q24") (pin "1") (pinfunction "S_1") (pintype "passive"))
      (node (ref "Q24") (pin "4") (pinfunction "S_4") (pintype "passive"))
      (node (ref "R148") (pin "2") (pinfunction "2_2") (pintype "passive"))
      (node (ref "R274") (pin "2") (pinfunction "2_2") (pintype "passive"))
    )
    (net (code "45") (name "GND") (class "Default")
      (node (ref "C100") (pin "1") (pinfunction "1_1") (pintype "passive"))
      (node (ref "C101") (pin "1") (pinfunction "1_1") (pintype "passive"))
      (node (ref "C103") (pin "1") (pinfunction "1_1") (pintype "passive"))
      (node (ref "C104") (pin "1") (pinfunction "1_1") (pintype "passive"))
      (node (ref "C107") (pin "1") (pinfunction "1_1") (pintype "passive"))
      (node (ref "C138") (pin "2") (pinfunction "2_2") (pintype "passive"))
      (node (ref "C148") (pin "1") (pinfunction "1_1") (pintype "passive"))
      (node (ref "C154") (pin "2") (pinfunction "2_2") (pintype "passive"))
      (node (ref "C158") (pin "1") (pinfunction "1_1") (pintype "passive"))
      (node (ref "C168") (pin "2") (pinfunction "2_2") (pintype "passive"))
      (node (ref "C19") (pin "1") (pinfunction "1_1") (pintype "passive"))
      (node (ref "C213") (pin "1") (pinfunction "1_1") (pintype "passive"))
      (node (ref "C233") (pin "1") (pinfunction "1_1") (pintype "passive"))
      (node (ref "C241") (pin "2") (pinfunction "2_2") (pintype "passive"))
      (node (ref "C242") (pin "2") (pinfunction "2_2") (pintype "passive"))
      (node (ref "C247") (pin "2") (pinfunction "2_2") (pintype "passive"))
      (node (ref "C262") (pin "2") (pinfunction "2_2") (pintype "passive"))
      (node (ref "C266") (pin "1") (pinfunction "1_1") (pintype "passive"))
      (node (ref "C268") (pin "1") (pinfunction "1_1") (pintype "passive"))
      (node (ref "C31") (pin "1") (pinfunction "1_1") (pintype "passive"))
      (node (ref "C34") (pin "2") (pinfunction "2_2") (pintype "passive"))
      (node (ref "C35") (pin "2") (pinfunction "2_2") (pintype "passive"))
      (node (ref "C67") (pin "2") (pinfunction "2_2") (pintype "passive"))
      (node (ref "C68") (pin "2") (pinfunction "2_2") (pintype "passive"))
      (node (ref "C69") (pin "2") (pinfunction "2_2") (pintype "passive"))
      (node (ref "C700") (pin "2") (pinfunction "2_2") (pintype "passive"))
      (node (ref "C701") (pin "2") (pinfunction "2_2") (pintype "passive"))
      (node (ref "C702") (pin "2") (pinfunction "2_2") (pintype "passive"))
      (node (ref "C703") (pin "2") (pinfunction "2_2") (pintype "passive"))
      (node (ref "C704") (pin "2") (pinfunction "2_2") (pintype "passive"))
      (node (ref "C705") (pin "2") (pinfunction "2_2") (pintype "passive"))
      (node (ref "C706") (pin "2") (pinfunction "2_2") (pintype "passive"))
      (node (ref "C707") (pin "2") (pinfunction "2_2") (pintype "passive"))
      (node (ref "C72") (pin "2") (pinfunction "2_2") (pintype "passive"))
      (node (ref "C73") (pin "2") (pinfunction "2_2") (pintype "passive"))
      (node (ref "C74") (pin "2") (pinfunction "2_2") (pintype "passive"))
      (node (ref "C75") (pin "2") (pinfunction "2_2") (pintype "passive"))
      (node (ref "C76") (pin "2") (pinfunction "2_2") (pintype "passive"))
      (node (ref "C77") (pin "2") (pinfunction "2_2") (pintype "passive"))
      (node (ref "C78") (pin "2") (pinfunction "2_2") (pintype "passive"))
      (node (ref "C780") (pin "2") (pinfunction "2_2") (pintype "passive"))
      (node (ref "C781") (pin "1") (pinfunction "1_1") (pintype "passive"))
      (node (ref "C782") (pin "2") (pinfunction "2_2") (pintype "passive"))
      (node (ref "C783") (pin "1") (pinfunction "1_1") (pintype "passive"))
      (node (ref "C784") (pin "2") (pinfunction "2_2") (pintype "passive"))
      (node (ref "C785") (pin "1") (pinfunction "1_1") (pintype "passive"))
      (node (ref "C786") (pin "2") (pinfunction "2_2") (pintype "passive"))
      (node (ref "C787") (pin "1") (pinfunction "1_1") (pintype "passive"))
      (node (ref "C79") (pin "2") (pinfunction "2_2") (pintype "passive"))
      (node (ref "C792") (pin "2") (pinfunction "2_2") (pintype "passive"))
      (node (ref "C793") (pin "1") (pinfunction "1_1") (pintype "passive"))
      (node (ref "C794") (pin "2") (pinfunction "2_2") (pintype "passive"))
      (node (ref "C795") (pin "1") (pinfunction "1_1") (pintype "passive"))
      (node (ref "C81") (pin "2") (pinfunction "2_2") (pintype "passive"))
      (node (ref "C88") (pin "1") (pinfunction "1_1") (pintype "passive"))
      (node (ref "C89") (pin "1") (pinfunction "1_1") (pintype "passive"))
      (node (ref "C90") (pin "1") (pinfunction "1_1") (pintype "passive"))
      (node (ref "C93") (pin "1") (pinfunction "1_1") (pintype "passive"))
      (node (ref "C94") (pin "1") (pinfunction "1_1") (pintype "passive"))
      (node (ref "C95") (pin "1") (pinfunction "1_1") (pintype "passive"))
      (node (ref "C96") (pin "1") (pinfunction "1_1") (pintype "passive"))
      (node (ref "C97") (pin "1") (pinfunction "1_1") (pintype "passive"))
      (node (ref "D2") (pin "2") (pinfunction "K_2") (pintype "passive"))
      (node (ref "JA11A") (pin "0") (pinfunction "0_0") (pintype "passive"))
      (node (ref "JA11A") (pin "5") (pinfunction "5_5") (pintype "passive"))
      (node (ref "JA11A") (pin "6") (pinfunction "6_6") (pintype "passive"))
      (node (ref "L10") (pin "2") (pinfunction "2_2") (pintype "passive"))
      (node (ref "L7") (pin "2") (pinfunction "2_2") (pintype "passive"))
      (node (ref "Q19") (pin "3") (pinfunction "D_3") (pintype "passive"))
      (node (ref "Q20") (pin "3") (pinfunction "D_3") (pintype "passive"))
      (node (ref "Q21") (pin "3") (pinfunction "D_3") (pintype "passive"))
      (node (ref "Q22") (pin "3") (pinfunction "D_3") (pintype "passive"))
      (node (ref "Q23") (pin "3") (pinfunction "D_3") (pintype "passive"))
      (node (ref "Q24") (pin "3") (pinfunction "D_3") (pintype "passive"))
      (node (ref "Q25") (pin "3") (pinfunction "D_3") (pintype "passive"))
      (node (ref "Q26") (pin "3") (pinfunction "D_3") (pintype "passive"))
      (node (ref "R110") (pin "1") (pinfunction "1_1") (pintype "passive"))
      (node (ref "R13") (pin "2") (pinfunction "2_2") (pintype "passive"))
      (node (ref "R133") (pin "2") (pinfunction "2_2") (pintype "passive"))
      (node (ref "R135") (pin "1") (pinfunction "1_1") (pintype "passive"))
      (node (ref "R150") (pin "2") (pinfunction "2_2") (pintype "passive"))
      (node (ref "R152") (pin "2") (pinfunction "2_2") (pintype "passive"))
      (node (ref "R16") (pin "2") (pinfunction "2_2") (pintype "passive"))
      (node (ref "R162") (pin "1") (pinfunction "1_1") (pintype "passive"))
      (node (ref "R17") (pin "2") (pinfunction "2_2") (pintype "passive"))
      (node (ref "R182") (pin "2") (pinfunction "2_2") (pintype "passive"))
      (node (ref "R192") (pin "1") (pinfunction "1_1") (pintype "passive"))
      (node (ref "R197") (pin "2") (pinfunction "2_2") (pintype "passive"))
      (node (ref "R2") (pin "1") (pinfunction "1_1") (pintype "passive"))
      (node (ref "R205") (pin "1") (pinfunction "1_1") (pintype "passive"))
      (node (ref "R207") (pin "2") (pinfunction "2_2") (pintype "passive"))
      (node (ref "R217") (pin "1") (pinfunction "1_1") (pintype "passive"))
      (node (ref "R219") (pin "2") (pinfunction "2_2") (pintype "passive"))
      (node (ref "R224") (pin "1") (pinfunction "1_1") (pintype "passive"))
      (node (ref "R248") (pin "2") (pinfunction "2_2") (pintype "passive"))
      (node (ref "R291") (pin "2") (pinfunction "2_2") (pintype "passive"))
      (node (ref "R31") (pin "1") (pinfunction "1_1") (pintype "passive"))
      (node (ref "R330") (pin "2") (pinfunction "2_2") (pintype "passive"))
      (node (ref "R333") (pin "1") (pinfunction "1_1") (pintype "passive"))
      (node (ref "R336") (pin "2") (pinfunction "2_2") (pintype "passive"))
      (node (ref "R44") (pin "2") (pinfunction "2_2") (pintype "passive"))
      (node (ref "R48") (pin "2") (pinfunction "2_2") (pintype "passive"))
      (node (ref "R5") (pin "1") (pinfunction "1_1") (pintype "passive"))
      (node (ref "R6") (pin "1") (pinfunction "1_1") (pintype "passive"))
      (node (ref "TP94") (pin "1") (pinfunction "1_1") (pintype "passive"))
      (node (ref "TP97") (pin "1") (pinfunction "1_1") (pintype "passive"))
    )
    (net (code "46") (name "Net-(C18-Pad2)") (class "Default")
      (node (ref "C18") (pin "2") (pinfunction "2_2") (pintype "passive"))
      (node (ref "R10") (pin "1") (pinfunction "1_1") (pintype "passive"))
    )
    (net (code "47") (name "Net-(C22-Pad2)") (class "Default")
      (node (ref "C22") (pin "2") (pinfunction "2_2") (pintype "passive"))
      (node (ref "C30") (pin "1") (pinfunction "1_1") (pintype "passive"))
      (node (ref "R22") (pin "1") (pinfunction "1_1") (pintype "passive"))
    )
    (net (code "48") (name "Net-(C36-Pad2)") (class "Default")
      (node (ref "C36") (pin "2") (pinfunction "2_2") (pintype "passive"))
      (node (ref "R25") (pin "1") (pinfunction "1_1") (pintype "passive"))
    )
    (net (code "49") (name "Net-(C133-Pad1)") (class "Default")
      (node (ref "C133") (pin "1") (pinfunction "1_1") (pintype "passive"))
      (node (ref "R122") (pin "1") (pinfunction "1_1") (pintype "passive"))
    )
    (net (code "50") (name "Net-(C140-Pad2)") (class "Default")
      (node (ref "C140") (pin "2") (pinfunction "2_2") (pintype "passive"))
      (node (ref "C30") (pin "2") (pinfunction "2_2") (pintype "passive"))
      (node (ref "R53") (pin "1") (pinfunction "1_1") (pintype "passive"))
    )
    (net (code "51") (name "Net-(C141-Pad1)") (class "Default")
      (node (ref "C141") (pin "1") (pinfunction "1_1") (pintype "passive"))
      (node (ref "R400") (pin "1") (pinfunction "1_1") (pintype "passive"))
    )
    (net (code "52") (name "Net-(C147-Pad2)") (class "Default")
      (node (ref "C147") (pin "2") (pinfunction "2_2") (pintype "passive"))
      (node (ref "R113") (pin "1") (pinfunction "1_1") (pintype "passive"))
    )
    (net (code "53") (name "Net-(C149-Pad2)") (class "Default")
      (node (ref "C149") (pin "2") (pinfunction "2_2") (pintype "passive"))
      (node (ref "R237") (pin "1") (pinfunction "1_1") (pintype "passive"))
    )
    (net (code "54") (name "Net-(C159-Pad2)") (class "Default")
      (node (ref "C159") (pin "2") (pinfunction "2_2") (pintype "passive"))
      (node (ref "C265") (pin "1") (pinfunction "1_1") (pintype "passive"))
      (node (ref "R156") (pin "1") (pinfunction "1_1") (pintype "passive"))
    )
    (net (code "55") (name "Net-(C226-Pad2)") (class "Default")
      (node (ref "C226") (pin "2") (pinfunction "2_2") (pintype "passive"))
      (node (ref "R249") (pin "1") (pinfunction "1_1") (pintype "passive"))
    )
    (net (code "56") (name "Net-(C231-Pad2)") (class "Default")
      (node (ref "C231") (pin "2") (pinfunction "2_2") (pintype "passive"))
      (node (ref "R265") (pin "1") (pinfunction "1_1") (pintype "passive"))
    )
    (net (code "57") (name "Net-(C265-Pad2)") (class "Default")
      (node (ref "C265") (pin "2") (pinfunction "2_2") (pintype "passive"))
      (node (ref "C269") (pin "2") (pinfunction "2_2") (pintype "passive"))
      (node (ref "R188") (pin "1") (pinfunction "1_1") (pintype "passive"))
    )
    (net (code "58") (name "Net-(C270-Pad2)") (class "Default")
      (node (ref "C270") (pin "2") (pinfunction "2_2") (pintype "passive"))
      (node (ref "R149") (pin "1") (pinfunction "1_1") (pintype "passive"))
    )
    (net (code "59") (name "Net-(C284-Pad2)") (class "Default")
      (node (ref "C284") (pin "2") (pinfunction "2_2") (pintype "passive"))
      (node (ref "R271") (pin "1") (pinfunction "1_1") (pintype "passive"))
    )
    (net (code "60") (name "Net-(D1-K)") (class "Default")
      (node (ref "D1") (pin "2") (pinfunction "K_2") (pintype "passive"))
      (node (ref "Q19") (pin "5") (pinfunction "G_5") (pintype "passive"))
      (node (ref "Q20") (pin "5") (pinfunction "G_5") (pintype "passive"))
      (node (ref "Q21") (pin "5") (pinfunction "G_5") (pintype "passive"))
      (node (ref "Q22") (pin "5") (pinfunction "G_5") (pintype "passive"))
      (node (ref "Q23") (pin "5") (pinfunction "G_5") (pintype "passive"))
      (node (ref "Q24") (pin "5") (pinfunction "G_5") (pintype "passive"))
      (node (ref "Q25") (pin "5") (pinfunction "G_5") (pintype "passive"))
      (node (ref "Q26") (pin "5") (pinfunction "G_5") (pintype "passive"))
      (node (ref "R198") (pin "2") (pinfunction "2_2") (pintype "passive"))
    )
    (net (code "61") (name "Net-(D2-A)") (class "Default")
      (node (ref "D2") (pin "1") (pinfunction "A_1") (pintype "passive"))
      (node (ref "Q19") (pin "2") (pinfunction "G_2") (pintype "passive"))
      (node (ref "Q20") (pin "2") (pinfunction "G_2") (pintype "passive"))
      (node (ref "Q21") (pin "2") (pinfunction "G_2") (pintype "passive"))
      (node (ref "Q22") (pin "2") (pinfunction "G_2") (pintype "passive"))
      (node (ref "Q23") (pin "2") (pinfunction "G_2") (pintype "passive"))
      (node (ref "Q24") (pin "2") (pinfunction "G_2") (pintype "passive"))
      (node (ref "Q25") (pin "2") (pinfunction "G_2") (pintype "passive"))
      (node (ref "Q26") (pin "2") (pinfunction "G_2") (pintype "passive"))
      (node (ref "R198") (pin "1") (pinfunction "1_1") (pintype "passive"))
    )
    (net (code "62") (name "Net-(D4-C)") (class "Default")
      (node (ref "C240") (pin "1") (pinfunction "1_1") (pintype "passive"))
      (node (ref "C792") (pin "1") (pinfunction "1_1") (pintype "passive"))
      (node (ref "D4") (pin "3") (pinfunction "C_3") (pintype "passive"))
      (node (ref "R1") (pin "2") (pinfunction "2_2") (pintype "passive"))
      (node (ref "R5") (pin "2") (pinfunction "2_2") (pintype "passive"))
    )
    (net (code "63") (name "Net-(D5-C)") (class "Default")
      (node (ref "C21") (pin "1") (pinfunction "1_1") (pintype "passive"))
      (node (ref "C793") (pin "2") (pinfunction "2_2") (pintype "passive"))
      (node (ref "D5") (pin "3") (pinfunction "C_3") (pintype "passive"))
      (node (ref "R13") (pin "1") (pinfunction "1_1") (pintype "passive"))
      (node (ref "R19") (pin "2") (pinfunction "2_2") (pintype "passive"))
    )
    (net (code "64") (name "Net-(D12-C)") (class "Default")
      (node (ref "C157") (pin "1") (pinfunction "1_1") (pintype "passive"))
      (node (ref "C794") (pin "1") (pinfunction "1_1") (pintype "passive"))
      (node (ref "D12") (pin "3") (pinfunction "C_3") (pintype "passive"))
      (node (ref "R110") (pin "2") (pinfunction "2_2") (pintype "passive"))
      (node (ref "R332") (pin "2") (pinfunction "2_2") (pintype "passive"))
    )
    (net (code "65") (name "Net-(D13-C)") (class "Default")
      (node (ref "C160") (pin "1") (pinfunction "1_1") (pintype "passive"))
      (node (ref "C795") (pin "2") (pinfunction "2_2") (pintype "passive"))
      (node (ref "D13") (pin "3") (pinfunction "C_3") (pintype "passive"))
      (node (ref "R133") (pin "1") (pinfunction "1_1") (pintype "passive"))
      (node (ref "R154") (pin "2") (pinfunction "2_2") (pintype "passive"))
    )
    (net (code "66") (name "Net-(D32-A)") (class "Default")
      (node (ref "D32") (pin "1") (pinfunction "A_1") (pintype "passive"))
      (node (ref "R24") (pin "1") (pinfunction "1_1") (pintype "passive"))
      (node (ref "R9") (pin "1") (pinfunction "1_1") (pintype "passive"))
    )
    (net (code "67") (name "Net-(D34-A)") (class "Default")
      (node (ref "D34") (pin "1") (pinfunction "A_1") (pintype "passive"))
      (node (ref "R51") (pin "1") (pinfunction "1_1") (pintype "passive"))
      (node (ref "R52") (pin "1") (pinfunction "1_1") (pintype "passive"))
    )
    (net (code "68") (name "Net-(J4-Pad1)") (class "Default")
      (node (ref "J4") (pin "1") (pinfunction "1_1") (pintype "passive"))
      (node (ref "J4") (pin "G") (pinfunction "G_G") (pintype "passive"))
      (node (ref "J4") (pin "RN") (pinfunction "RN_RN") (pintype "passive"))
      (node (ref "J4") (pin "S") (pinfunction "S_S") (pintype "passive"))
      (node (ref "J4") (pin "SN") (pinfunction "SN_SN") (pintype "passive"))
      (node (ref "J4") (pin "TN") (pinfunction "TN_TN") (pintype "passive"))
      (node (ref "L7") (pin "1") (pinfunction "1_1") (pintype "passive"))
    )
    (net (code "69") (name "Net-(J5-Pad1)") (class "Default")
      (node (ref "J5") (pin "1") (pinfunction "1_1") (pintype "passive"))
      (node (ref "J5") (pin "G") (pinfunction "G_G") (pintype "passive"))
      (node (ref "J5") (pin "RN") (pinfunction "RN_RN") (pintype "passive"))
      (node (ref "J5") (pin "S") (pinfunction "S_S") (pintype "passive"))
      (node (ref "J5") (pin "SN") (pinfunction "SN_SN") (pintype "passive"))
      (node (ref "J5") (pin "TN") (pinfunction "TN_TN") (pintype "passive"))
      (node (ref "L10") (pin "1") (pinfunction "1_1") (pintype "passive"))
    )
    (net (code "70") (name "Net-(Q7A-E)") (class "Default")
      (node (ref "C32") (pin "1") (pinfunction "1_1") (pintype "passive"))
      (node (ref "Q7") (pin "1") (pinfunction "E_1") (pintype "passive"))
      (node (ref "Q8") (pin "1") (pinfunction "E_1") (pintype "passive"))
      (node (ref "Q9") (pin "1") (pinfunction "E_1") (pintype "passive"))
      (node (ref "R300") (pin "1") (pinfunction "1_1") (pintype "passive"))
      (node (ref "R41") (pin "1") (pinfunction "1_1") (pintype "passive"))
      (node (ref "TP36") (pin "1") (pinfunction "1_1") (pintype "passive"))
    )
    (net (code "71") (name "Net-(Q7B-E)") (class "Default")
      (node (ref "C17") (pin "1") (pinfunction "1_1") (pintype "passive"))
      (node (ref "Q7") (pin "4") (pinfunction "E_4") (pintype "passive"))
      (node (ref "Q8") (pin "4") (pinfunction "E_4") (pintype "passive"))
      (node (ref "Q9") (pin "4") (pinfunction "E_4") (pintype "passive"))
      (node (ref "R122") (pin "2") (pinfunction "2_2") (pintype "passive"))
      (node (ref "R3") (pin "1") (pinfunction "1_1") (pintype "passive"))
      (node (ref "TP31") (pin "1") (pinfunction "1_1") (pintype "passive"))
    )
    (net (code "72") (name "Net-(Q11A-E)") (class "Default")
      (node (ref "C267") (pin "1") (pinfunction "1_1") (pintype "passive"))
      (node (ref "Q11") (pin "1") (pinfunction "E_1") (pintype "passive"))
      (node (ref "Q12") (pin "1") (pinfunction "E_1") (pintype "passive"))
      (node (ref "Q13") (pin "1") (pinfunction "E_1") (pintype "passive"))
      (node (ref "R166") (pin "1") (pinfunction "1_1") (pintype "passive"))
      (node (ref "R175") (pin "1") (pinfunction "1_1") (pintype "passive"))
      (node (ref "TP49") (pin "1") (pinfunction "1_1") (pintype "passive"))
    )
    (net (code "73") (name "Net-(Q11B-E)") (class "Default")
      (node (ref "C144") (pin "1") (pinfunction "1_1") (pintype "passive"))
      (node (ref "Q11") (pin "4") (pinfunction "E_4") (pintype "passive"))
      (node (ref "Q12") (pin "4") (pinfunction "E_4") (pintype "passive"))
      (node (ref "Q13") (pin "4") (pinfunction "E_4") (pintype "passive"))
      (node (ref "R131") (pin "1") (pinfunction "1_1") (pintype "passive"))
      (node (ref "R400") (pin "2") (pinfunction "2_2") (pintype "passive"))
      (node (ref "TP44") (pin "1") (pinfunction "1_1") (pintype "passive"))
    )
    (net (code "74") (name "Net-(U1A-IN+)") (class "Default")
      (node (ref "C240") (pin "2") (pinfunction "2_2") (pintype "passive"))
      (node (ref "C289") (pin "2") (pinfunction "2_2") (pintype "passive"))
      (node (ref "R6") (pin "2") (pinfunction "2_2") (pintype "passive"))
      (node (ref "U1") (pin "3") (pinfunction "IN+_3") (pintype "input"))
    )
    (net (code "75") (name "Net-(U1A-IN-)") (class "Default")
      (node (ref "C289") (pin "1") (pinfunction "1_1") (pintype "passive"))
      (node (ref "R220") (pin "1") (pinfunction "1_1") (pintype "passive"))
      (node (ref "U1") (pin "1") (pinfunction "OUT_1") (pintype "output"))
      (node (ref "U1") (pin "2") (pinfunction "IN-_2") (pintype "input"))
    )
    (net (code "76") (name "Net-(U1B-IN+)") (class "Default")
      (node (ref "C21") (pin "2") (pinfunction "2_2") (pintype "passive"))
      (node (ref "C290") (pin "2") (pinfunction "2_2") (pintype "passive"))
      (node (ref "R16") (pin "1") (pinfunction "1_1") (pintype "passive"))
      (node (ref "U1") (pin "5") (pinfunction "IN+_5") (pintype "input"))
    )
    (net (code "77") (name "Net-(U1B-IN-)") (class "Default")
      (node (ref "C290") (pin "1") (pinfunction "1_1") (pintype "passive"))
      (node (ref "R236") (pin "1") (pinfunction "1_1") (pintype "passive"))
      (node (ref "U1") (pin "6") (pinfunction "IN-_6") (pintype "input"))
      (node (ref "U1") (pin "7") (pinfunction "OUT_7") (pintype "output"))
    )
    (net (code "78") (name "Net-(U1C-IN+)") (class "Default")
      (node (ref "C158") (pin "2") (pinfunction "2_2") (pintype "passive"))
      (node (ref "R146") (pin "1") (pinfunction "1_1") (pintype "passive"))
      (node (ref "U1") (pin "10") (pinfunction "IN+_10") (pintype "input"))
    )
    (net (code "79") (name "Net-(U1C-IN-)") (class "Default")
      (node (ref "C170") (pin "2") (pinfunction "2_2") (pintype "passive"))
      (node (ref "R142") (pin "1") (pinfunction "1_1") (pintype "passive"))
      (node (ref "U1") (pin "9") (pinfunction "IN-_9") (pintype "input"))
    )
    (net (code "80") (name "Net-(U1C-OUT)") (class "Default")
      (node (ref "C170") (pin "1") (pinfunction "1_1") (pintype "passive"))
      (node (ref "R189") (pin "2") (pinfunction "2_2") (pintype "passive"))
      (node (ref "R194") (pin "1") (pinfunction "1_1") (pintype "passive"))
      (node (ref "U1") (pin "8") (pinfunction "OUT_8") (pintype "output"))
    )
    (net (code "81") (name "Net-(U1D-IN+)") (class "Default")
      (node (ref "C213") (pin "2") (pinfunction "2_2") (pintype "passive"))
      (node (ref "R331") (pin "1") (pinfunction "1_1") (pintype "passive"))
      (node (ref "U1") (pin "12") (pinfunction "IN+_12") (pintype "input"))
    )
    (net (code "82") (name "Net-(U1D-IN-)") (class "Default")
      (node (ref "C244") (pin "2") (pinfunction "2_2") (pintype "passive"))
      (node (ref "R200") (pin "1") (pinfunction "1_1") (pintype "passive"))
      (node (ref "U1") (pin "13") (pinfunction "IN-_13") (pintype "input"))
    )
    (net (code "83") (name "Net-(U1D-OUT)") (class "Default")
      (node (ref "C244") (pin "1") (pinfunction "1_1") (pintype "passive"))
      (node (ref "R202") (pin "2") (pinfunction "2_2") (pintype "passive"))
      (node (ref "R206") (pin "1") (pinfunction "1_1") (pintype "passive"))
      (node (ref "U1") (pin "14") (pinfunction "OUT_14") (pintype "output"))
    )
    (net (code "84") (name "Net-(U2A-IN+)") (class "Default")
      (node (ref "R192") (pin "2") (pinfunction "2_2") (pintype "passive"))
      (node (ref "R194") (pin "2") (pinfunction "2_2") (pintype "passive"))
      (node (ref "U2") (pin "3") (pinfunction "IN+_3") (pintype "passive"))
    )
    (net (code "85") (name "Net-(U2A-IN-)") (class "Default")
      (node (ref "C18") (pin "1") (pinfunction "1_1") (pintype "passive"))
      (node (ref "R18") (pin "2") (pinfunction "2_2") (pintype "passive"))
      (node (ref "R7") (pin "1") (pinfunction "1_1") (pintype "passive"))
      (node (ref "TP32") (pin "1") (pinfunction "1_1") (pintype "passive"))
      (node (ref "U2") (pin "2") (pinfunction "IN-_2") (pintype "passive"))
    )
    (net (code "86") (name "Net-(U2A-OUT)") (class "Default")
      (node (ref "C149") (pin "1") (pinfunction "1_1") (pintype "passive"))
      (node (ref "R10") (pin "2") (pinfunction "2_2") (pintype "passive"))
      (node (ref "R3") (pin "2") (pinfunction "2_2") (pintype "passive"))
      (node (ref "R7") (pin "2") (pinfunction "2_2") (pintype "passive"))
      (node (ref "U2") (pin "1") (pinfunction "OUT_1") (pintype "passive"))
    )
    (net (code "87") (name "Net-(U2B-IN+)") (class "Default")
      (node (ref "R205") (pin "2") (pinfunction "2_2") (pintype "passive"))
      (node (ref "R206") (pin "2") (pinfunction "2_2") (pintype "passive"))
      (node (ref "U2") (pin "5") (pinfunction "IN+_5") (pintype "passive"))
    )
    (net (code "88") (name "Net-(U2B-IN-)") (class "Default")
      (node (ref "C36") (pin "1") (pinfunction "1_1") (pintype "passive"))
      (node (ref "R45") (pin "1") (pinfunction "1_1") (pintype "passive"))
      (node (ref "R50") (pin "2") (pinfunction "2_2") (pintype "passive"))
      (node (ref "TP37") (pin "1") (pinfunction "1_1") (pintype "passive"))
      (node (ref "U2") (pin "6") (pinfunction "IN-_6") (pintype "passive"))
    )
    (net (code "89") (name "Net-(U2B-OUT)") (class "Default")
      (node (ref "C226") (pin "1") (pinfunction "1_1") (pintype "passive"))
      (node (ref "R25") (pin "2") (pinfunction "2_2") (pintype "passive"))
      (node (ref "R41") (pin "2") (pinfunction "2_2") (pintype "passive"))
      (node (ref "R45") (pin "2") (pinfunction "2_2") (pintype "passive"))
      (node (ref "U2") (pin "7") (pinfunction "OUT_7") (pintype "passive"))
    )
    (net (code "90") (name "Net-(U4A-IN+)") (class "Default")
      (node (ref "C157") (pin "2") (pinfunction "2_2") (pintype "passive"))
      (node (ref "C297") (pin "2") (pinfunction "2_2") (pintype "passive"))
      (node (ref "R135") (pin "2") (pinfunction "2_2") (pintype "passive"))
      (node (ref "U4") (pin "3") (pinfunction "IN+_3") (pintype "input"))
    )
    (net (code "91") (name "Net-(U4A-IN-)") (class "Default")
      (node (ref "C297") (pin "1") (pinfunction "1_1") (pintype "passive"))
      (node (ref "R253") (pin "1") (pinfunction "1_1") (pintype "passive"))
      (node (ref "U4") (pin "1") (pinfunction "OUT_1") (pintype "output"))
      (node (ref "U4") (pin "2") (pinfunction "IN-_2") (pintype "input"))
    )
    (net (code "92") (name "Net-(U4B-IN+)") (class "Default")
      (node (ref "C160") (pin "2") (pinfunction "2_2") (pintype "passive"))
      (node (ref "C302") (pin "2") (pinfunction "2_2") (pintype "passive"))
      (node (ref "R150") (pin "1") (pinfunction "1_1") (pintype "passive"))
      (node (ref "U4") (pin "5") (pinfunction "IN+_5") (pintype "input"))
    )
    (net (code "93") (name "Net-(U4B-IN-)") (class "Default")
      (node (ref "C302") (pin "1") (pinfunction "1_1") (pintype "passive"))
      (node (ref "R264") (pin "1") (pinfunction "1_1") (pintype "passive"))
      (node (ref "U4") (pin "6") (pinfunction "IN-_6") (pintype "input"))
      (node (ref "U4") (pin "7") (pinfunction "OUT_7") (pintype "output"))
    )
    (net (code "94") (name "Net-(U4C-IN+)") (class "Default")
      (node (ref "C233") (pin "2") (pinfunction "2_2") (pintype "passive"))
      (node (ref "R334") (pin "1") (pinfunction "1_1") (pintype "passive"))
      (node (ref "U4") (pin "10") (pinfunction "IN+_10") (pintype "input"))
    )
    (net (code "95") (name "Net-(U4C-IN-)") (class "Default")
      (node (ref "C258") (pin "2") (pinfunction "2_2") (pintype "passive"))
      (node (ref "R211") (pin "1") (pinfunction "1_1") (pintype "passive"))
      (node (ref "U4") (pin "9") (pinfunction "IN-_9") (pintype "input"))
    )
    (net (code "96") (name "Net-(U4C-OUT)") (class "Default")
      (node (ref "C258") (pin "1") (pinfunction "1_1") (pintype "passive"))
      (node (ref "R215") (pin "2") (pinfunction "2_2") (pintype "passive"))
      (node (ref "R218") (pin "1") (pinfunction "1_1") (pintype "passive"))
      (node (ref "U4") (pin "8") (pinfunction "OUT_8") (pintype "output"))
    )
    (net (code "97") (name "Net-(U4D-IN+)") (class "Default")
      (node (ref "C268") (pin "2") (pinfunction "2_2") (pintype "passive"))
      (node (ref "R148") (pin "1") (pinfunction "1_1") (pintype "passive"))
      (node (ref "U4") (pin "12") (pinfunction "IN+_12") (pintype "input"))
    )
    (net (code "98") (name "Net-(U4D-IN-)") (class "Default")
      (node (ref "C172") (pin "2") (pinfunction "2_2") (pintype "passive"))
      (node (ref "R221") (pin "1") (pinfunction "1_1") (pintype "passive"))
      (node (ref "U4") (pin "13") (pinfunction "IN-_13") (pintype "input"))
    )
    (net (code "99") (name "Net-(U4D-OUT)") (class "Default")
      (node (ref "C172") (pin "1") (pinfunction "1_1") (pintype "passive"))
      (node (ref "R222") (pin "2") (pinfunction "2_2") (pintype "passive"))
      (node (ref "R238") (pin "1") (pinfunction "1_1") (pintype "passive"))
      (node (ref "U4") (pin "14") (pinfunction "OUT_14") (pintype "output"))
    )
    (net (code "100") (name "Net-(U5A-IN+)") (class "Default")
      (node (ref "R217") (pin "2") (pinfunction "2_2") (pintype "passive"))
      (node (ref "R218") (pin "2") (pinfunction "2_2") (pintype "passive"))
      (node (ref "U5") (pin "3") (pinfunction "IN+_3") (pintype "passive"))
    )
    (net (code "101") (name "Net-(U5A-IN-)") (class "Default")
      (node (ref "C147") (pin "1") (pinfunction "1_1") (pintype "passive"))
      (node (ref "R144") (pin "1") (pinfunction "1_1") (pintype "passive"))
      (node (ref "R153") (pin "2") (pinfunction "2_2") (pintype "passive"))
      (node (ref "TP45") (pin "1") (pinfunction "1_1") (pintype "passive"))
      (node (ref "U5") (pin "2") (pinfunction "IN-_2") (pintype "passive"))
    )
    (net (code "102") (name "Net-(U5A-OUT)") (class "Default")
      (node (ref "C231") (pin "1") (pinfunction "1_1") (pintype "passive"))
      (node (ref "R113") (pin "2") (pinfunction "2_2") (pintype "passive"))
      (node (ref "R131") (pin "2") (pinfunction "2_2") (pintype "passive"))
      (node (ref "R144") (pin "2") (pinfunction "2_2") (pintype "passive"))
      (node (ref "U5") (pin "1") (pinfunction "OUT_1") (pintype "passive"))
    )
    (net (code "103") (name "Net-(U5B-IN+)") (class "Default")
      (node (ref "R224") (pin "2") (pinfunction "2_2") (pintype "passive"))
      (node (ref "R238") (pin "2") (pinfunction "2_2") (pintype "passive"))
      (node (ref "U5") (pin "5") (pinfunction "IN+_5") (pintype "passive"))
    )
    (net (code "104") (name "Net-(U5B-IN-)") (class "Default")
      (node (ref "C270") (pin "1") (pinfunction "1_1") (pintype "passive"))
      (node (ref "R178") (pin "1") (pinfunction "1_1") (pintype "passive"))
      (node (ref "R186") (pin "2") (pinfunction "2_2") (pintype "passive"))
      (node (ref "TP50") (pin "1") (pinfunction "1_1") (pintype "passive"))
      (node (ref "U5") (pin "6") (pinfunction "IN-_6") (pintype "passive"))
    )
    (net (code "105") (name "Net-(U5B-OUT)") (class "Default")
      (node (ref "C284") (pin "1") (pinfunction "1_1") (pintype "passive"))
      (node (ref "R149") (pin "2") (pinfunction "2_2") (pintype "passive"))
      (node (ref "R175") (pin "2") (pinfunction "2_2") (pintype "passive"))
      (node (ref "R178") (pin "2") (pinfunction "2_2") (pintype "passive"))
      (node (ref "U5") (pin "7") (pinfunction "OUT_7") (pintype "passive"))
    )
    (net (code "106") (name "Net-(U48A-IN+)") (class "Default")
      (node (ref "C292") (pin "2") (pinfunction "2_2") (pintype "passive"))
      (node (ref "C34") (pin "1") (pinfunction "1_1") (pintype "passive"))
      (node (ref "R197") (pin "1") (pinfunction "1_1") (pintype "passive"))
      (node (ref "R42") (pin "2") (pinfunction "2_2") (pintype "passive"))
      (node (ref "R44") (pin "1") (pinfunction "1_1") (pintype "passive"))
      (node (ref "U48") (pin "3") (pinfunction "IN+_3") (pintype "passive"))
    )
    (net (code "107") (name "Net-(U48A-IN-)") (class "Default")
      (node (ref "C24") (pin "1") (pinfunction "1_1") (pintype "passive"))
      (node (ref "C292") (pin "1") (pinfunction "1_1") (pintype "passive"))
      (node (ref "R189") (pin "1") (pinfunction "1_1") (pintype "passive"))
      (node (ref "R26") (pin "1") (pinfunction "1_1") (pintype "passive"))
      (node (ref "R32") (pin "2") (pinfunction "2_2") (pintype "passive"))
      (node (ref "U48") (pin "2") (pinfunction "IN-_2") (pintype "passive"))
    )
    (net (code "108") (name "Net-(U48A-OUT)") (class "Default")
      (node (ref "C24") (pin "2") (pinfunction "2_2") (pintype "passive"))
      (node (ref "R239") (pin "1") (pinfunction "1_1") (pintype "passive"))
      (node (ref "R26") (pin "2") (pinfunction "2_2") (pintype "passive"))
      (node (ref "U48") (pin "1") (pinfunction "OUT_1") (pintype "passive"))
    )
    (net (code "109") (name "Net-(U48B-IN+)") (class "Default")
      (node (ref "C293") (pin "2") (pinfunction "2_2") (pintype "passive"))
      (node (ref "C35") (pin "1") (pinfunction "1_1") (pintype "passive"))
      (node (ref "R207") (pin "1") (pinfunction "1_1") (pintype "passive"))
      (node (ref "R329") (pin "2") (pinfunction "2_2") (pintype "passive"))
      (node (ref "R330") (pin "1") (pinfunction "1_1") (pintype "passive"))
      (node (ref "U48") (pin "5") (pinfunction "IN+_5") (pintype "passive"))
    )
    (net (code "110") (name "Net-(U48B-IN-)") (class "Default")
      (node (ref "C243") (pin "1") (pinfunction "1_1") (pintype "passive"))
      (node (ref "C293") (pin "1") (pinfunction "1_1") (pintype "passive"))
      (node (ref "R202") (pin "1") (pinfunction "1_1") (pintype "passive"))
      (node (ref "R327") (pin "1") (pinfunction "1_1") (pintype "passive"))
      (node (ref "R33") (pin "2") (pinfunction "2_2") (pintype "passive"))
      (node (ref "U48") (pin "6") (pinfunction "IN-_6") (pintype "passive"))
    )
    (net (code "111") (name "Net-(U48B-OUT)") (class "Default")
      (node (ref "C243") (pin "2") (pinfunction "2_2") (pintype "passive"))
      (node (ref "R252") (pin "1") (pinfunction "1_1") (pintype "passive"))
      (node (ref "R327") (pin "2") (pinfunction "2_2") (pintype "passive"))
      (node (ref "U48") (pin "7") (pinfunction "OUT_7") (pintype "passive"))
    )
    (net (code "112") (name "Net-(U49A-IN+)") (class "Default")
      (node (ref "C154") (pin "1") (pinfunction "1_1") (pintype "passive"))
      (node (ref "C303") (pin "2") (pinfunction "2_2") (pintype "passive"))
      (node (ref "R219") (pin "1") (pinfunction "1_1") (pintype "passive"))
      (node (ref "R290") (pin "2") (pinfunction "2_2") (pintype "passive"))
      (node (ref "R291") (pin "1") (pinfunction "1_1") (pintype "passive"))
      (node (ref "U49") (pin "3") (pinfunction "IN+_3") (pintype "passive"))
    )
    (net (code "113") (name "Net-(U49A-IN-)") (class "Default")
      (node (ref "C255") (pin "1") (pinfunction "1_1") (pintype "passive"))
      (node (ref "C303") (pin "1") (pinfunction "1_1") (pintype "passive"))
      (node (ref "R215") (pin "1") (pinfunction "1_1") (pintype "passive"))
      (node (ref "R284") (pin "1") (pinfunction "1_1") (pintype "passive"))
      (node (ref "R286") (pin "2") (pinfunction "2_2") (pintype "passive"))
      (node (ref "U49") (pin "2") (pinfunction "IN-_2") (pintype "passive"))
    )
    (net (code "114") (name "Net-(U49A-OUT)") (class "Default")
      (node (ref "C255") (pin "2") (pinfunction "2_2") (pintype "passive"))
      (node (ref "R269") (pin "1") (pinfunction "1_1") (pintype "passive"))
      (node (ref "R284") (pin "2") (pinfunction "2_2") (pintype "passive"))
      (node (ref "U49") (pin "1") (pinfunction "OUT_1") (pintype "passive"))
    )
    (net (code "115") (name "Net-(U49B-IN+)") (class "Default")
      (node (ref "C168") (pin "1") (pinfunction "1_1") (pintype "passive"))
      (node (ref "C305") (pin "2") (pinfunction "2_2") (pintype "passive"))
      (node (ref "R248") (pin "1") (pinfunction "1_1") (pintype "passive"))
      (node (ref "R294") (pin "2") (pinfunction "2_2") (pintype "passive"))
      (node (ref "R336") (pin "1") (pinfunction "1_1") (pintype "passive"))
      (node (ref "U49") (pin "5") (pinfunction "IN+_5") (pintype "passive"))
    )
    (net (code "116") (name "Net-(U49B-IN-)") (class "Default")
      (node (ref "C155") (pin "1") (pinfunction "1_1") (pintype "passive"))
      (node (ref "C305") (pin "1") (pinfunction "1_1") (pintype "passive"))
      (node (ref "R222") (pin "1") (pinfunction "1_1") (pintype "passive"))
      (node (ref "R292") (pin "1") (pinfunction "1_1") (pintype "passive"))
      (node (ref "R34") (pin "2") (pinfunction "2_2") (pintype "passive"))
      (node (ref "U49") (pin "6") (pinfunction "IN-_6") (pintype "passive"))
    )
    (net (code "117") (name "Net-(U49B-OUT)") (class "Default")
      (node (ref "C155") (pin "2") (pinfunction "2_2") (pintype "passive"))
      (node (ref "R274") (pin "1") (pinfunction "1_1") (pintype "passive"))
      (node (ref "R292") (pin "2") (pinfunction "2_2") (pintype "passive"))
      (node (ref "U49") (pin "7") (pinfunction "OUT_7") (pintype "passive"))
    )
    (net (code "118") (name "unconnected-(D32-C-Pad3)") (class "Default")
      (node (ref "D32") (pin "3") (pinfunction "C_3") (pintype "passive"))
    )
    (net (code "119") (name "unconnected-(D34-C-Pad3)") (class "Default")
      (node (ref "D34") (pin "3") (pinfunction "C_3") (pintype "passive"))
    )
  )
)
